# PCB0M3_12B.net
KiCad netlist of a schematic drawn in EAGLE
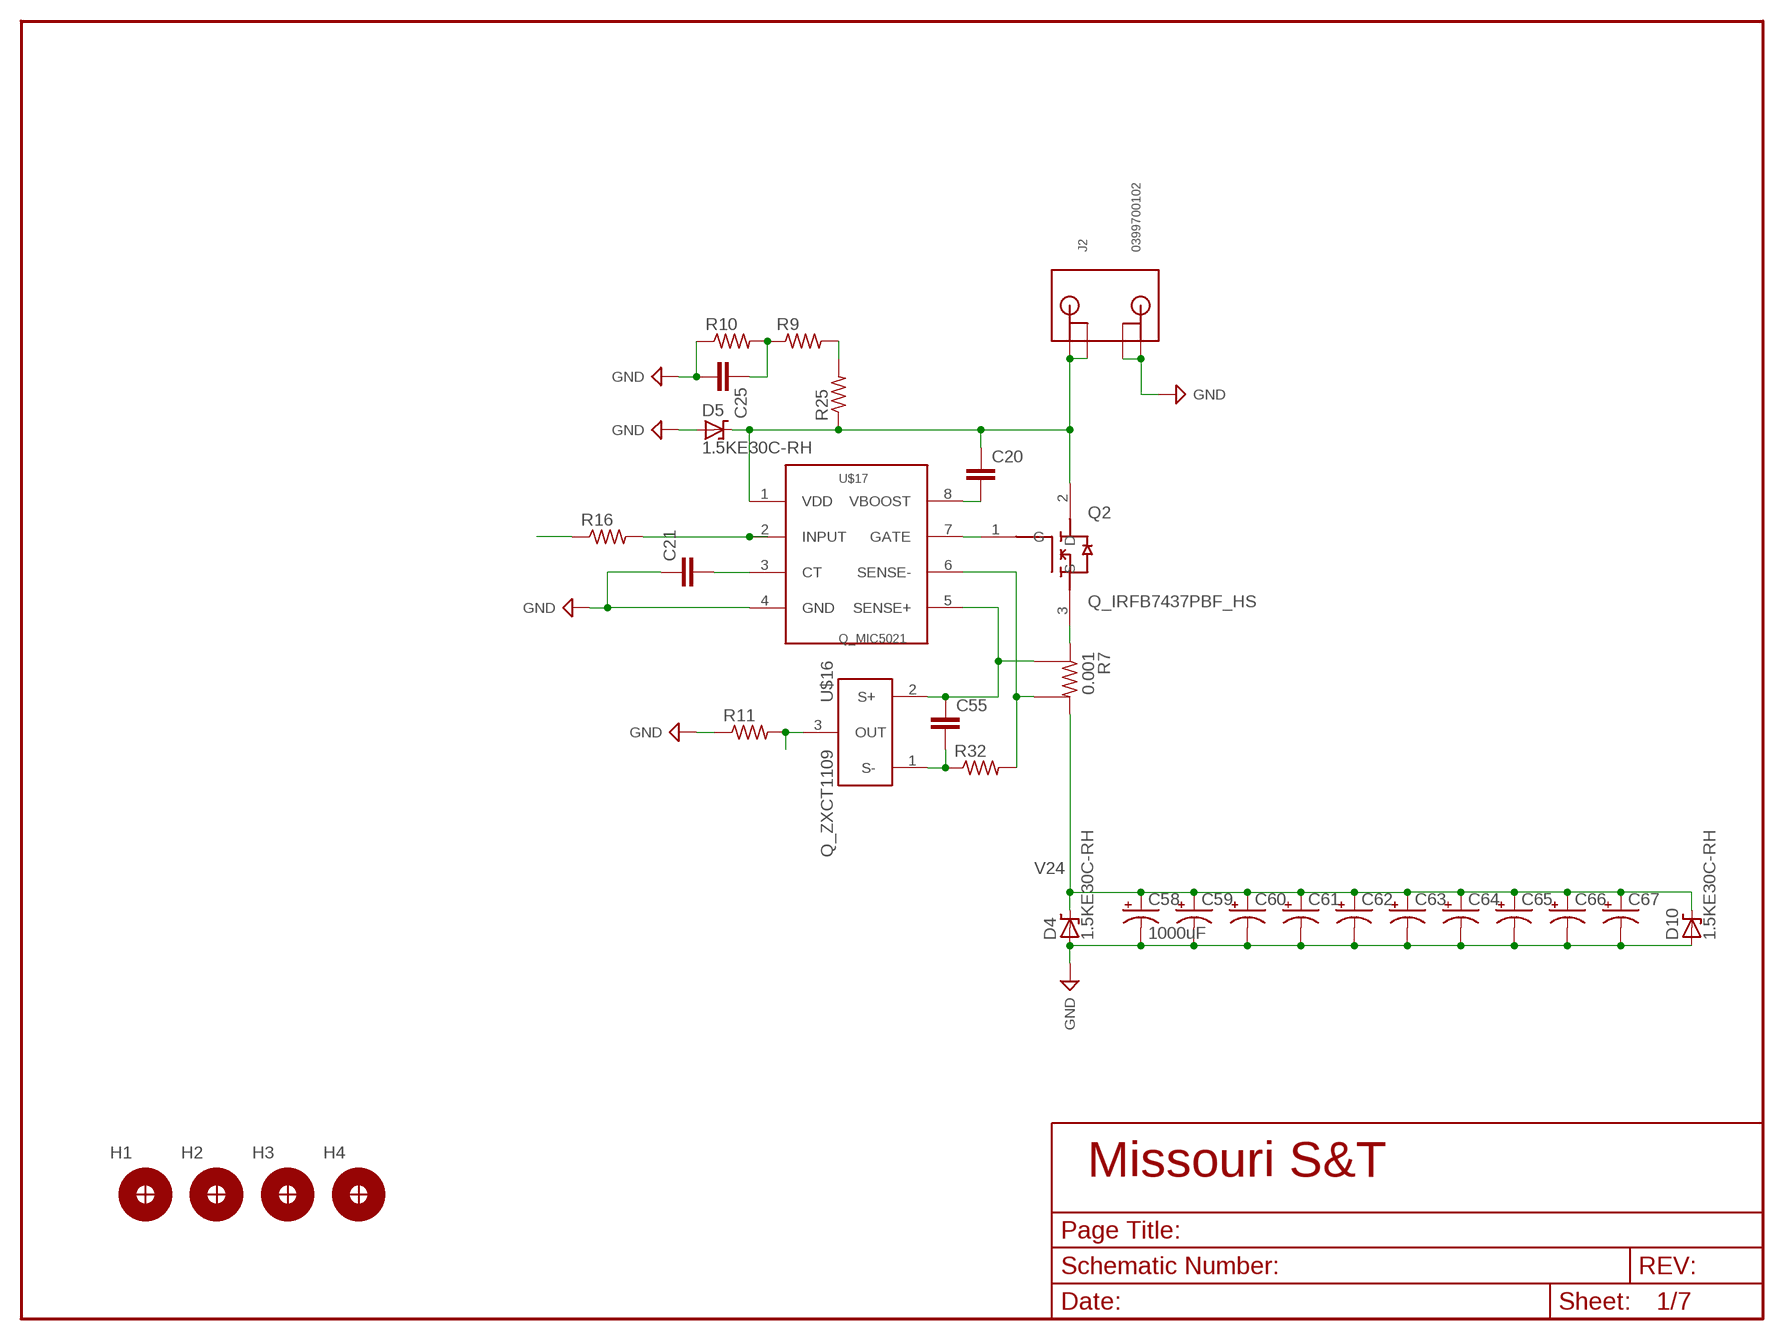
[diagram p0: schematic, sheet 1]
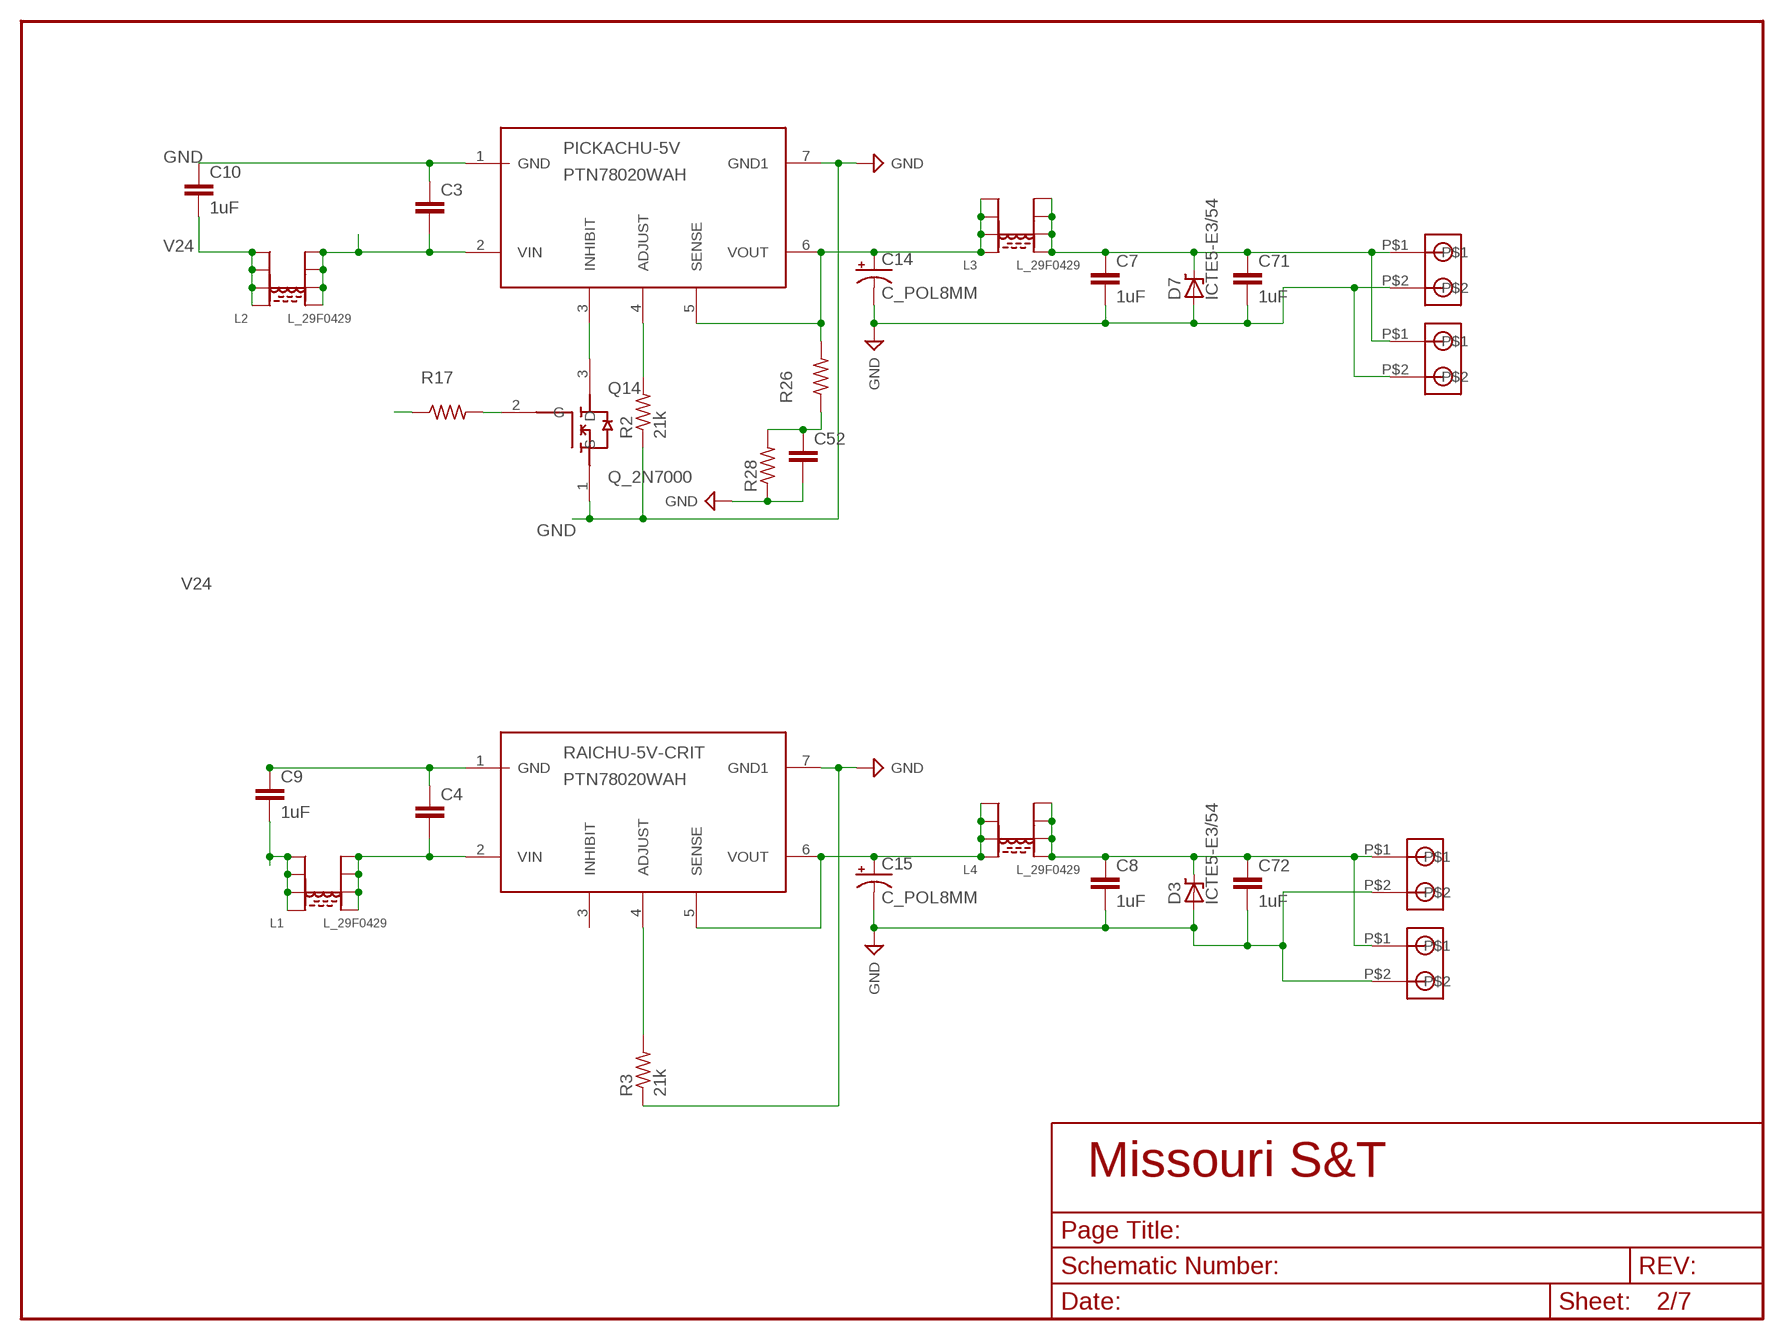
[diagram p1: schematic, sheet 2]
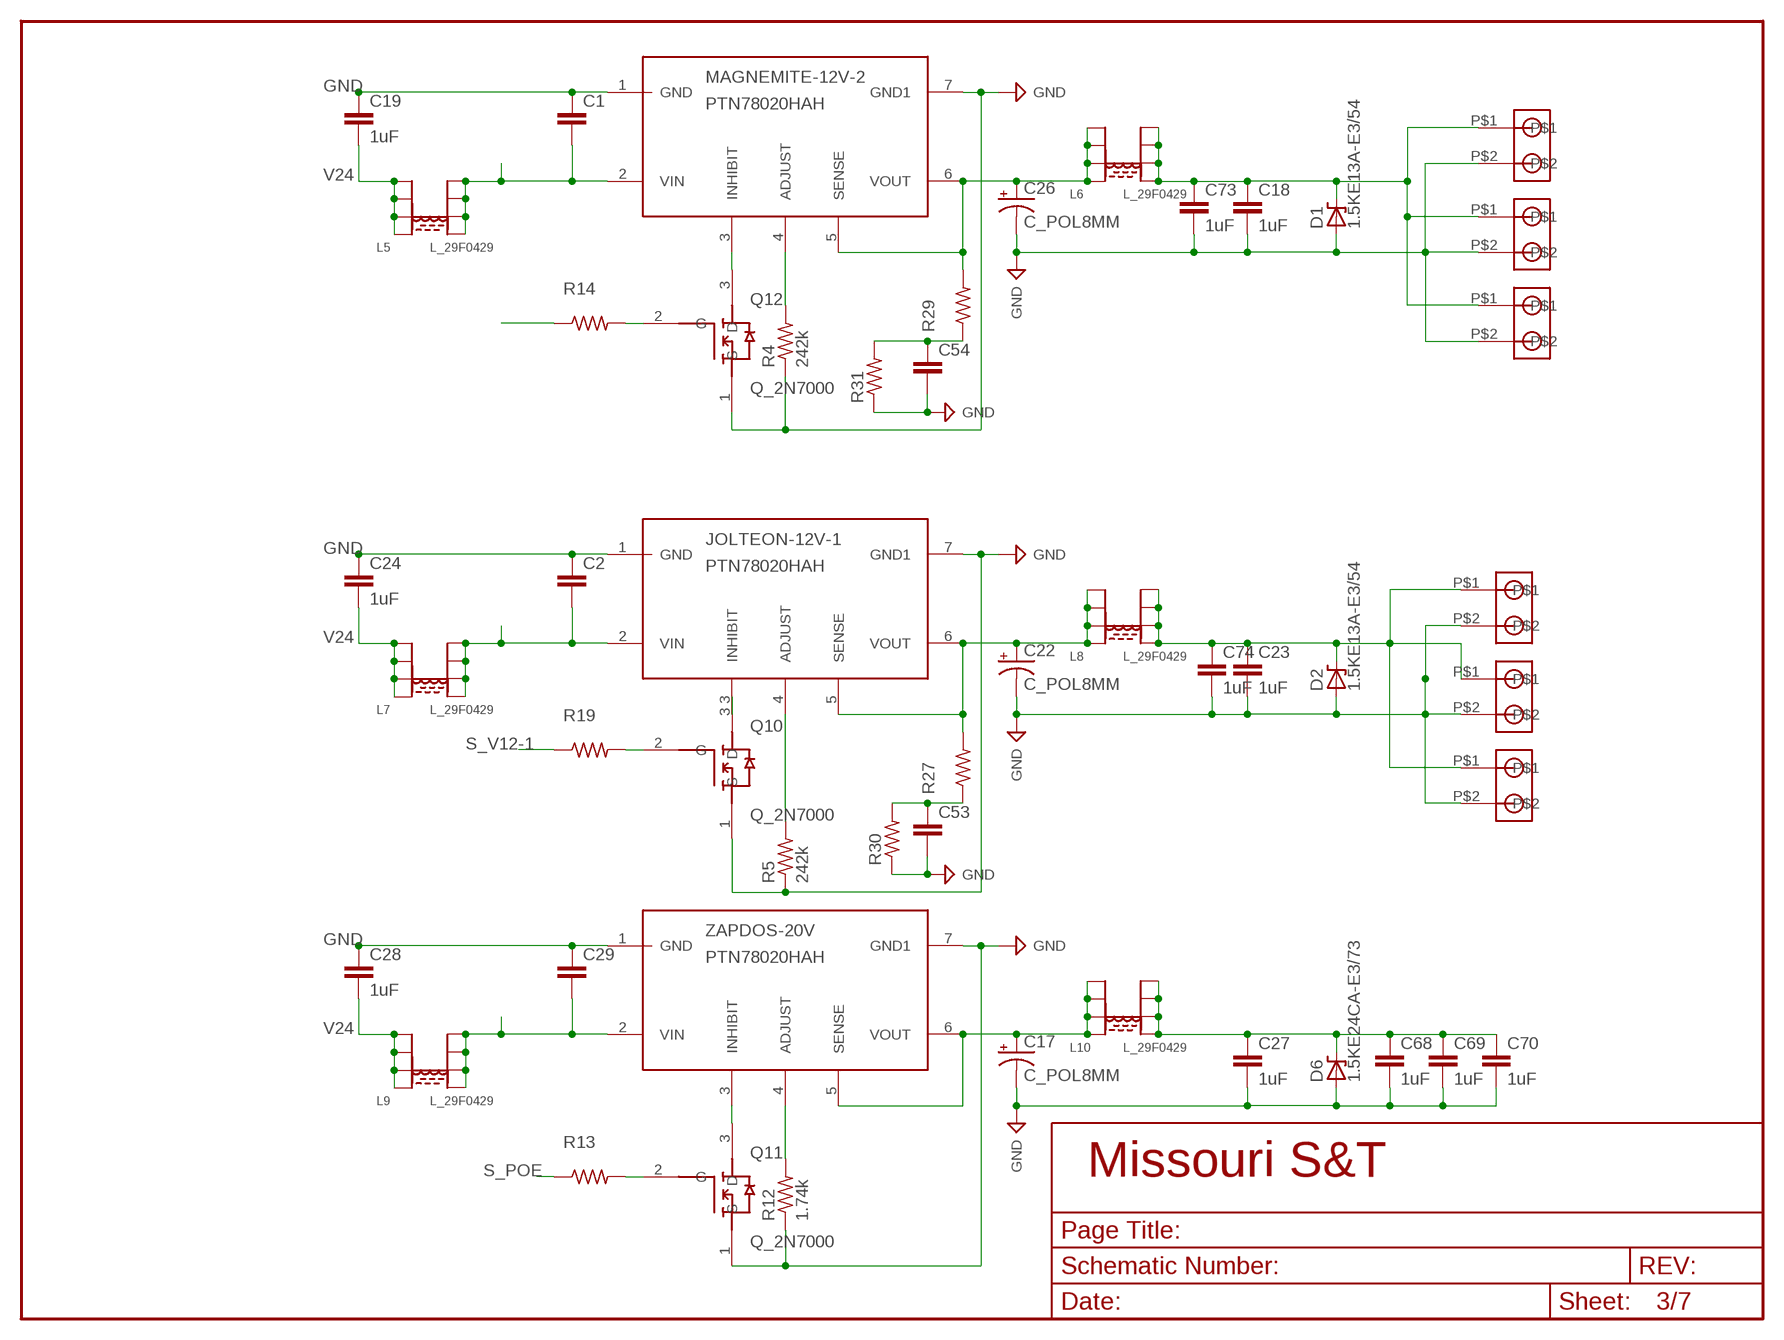
[diagram p2: schematic, sheet 3]
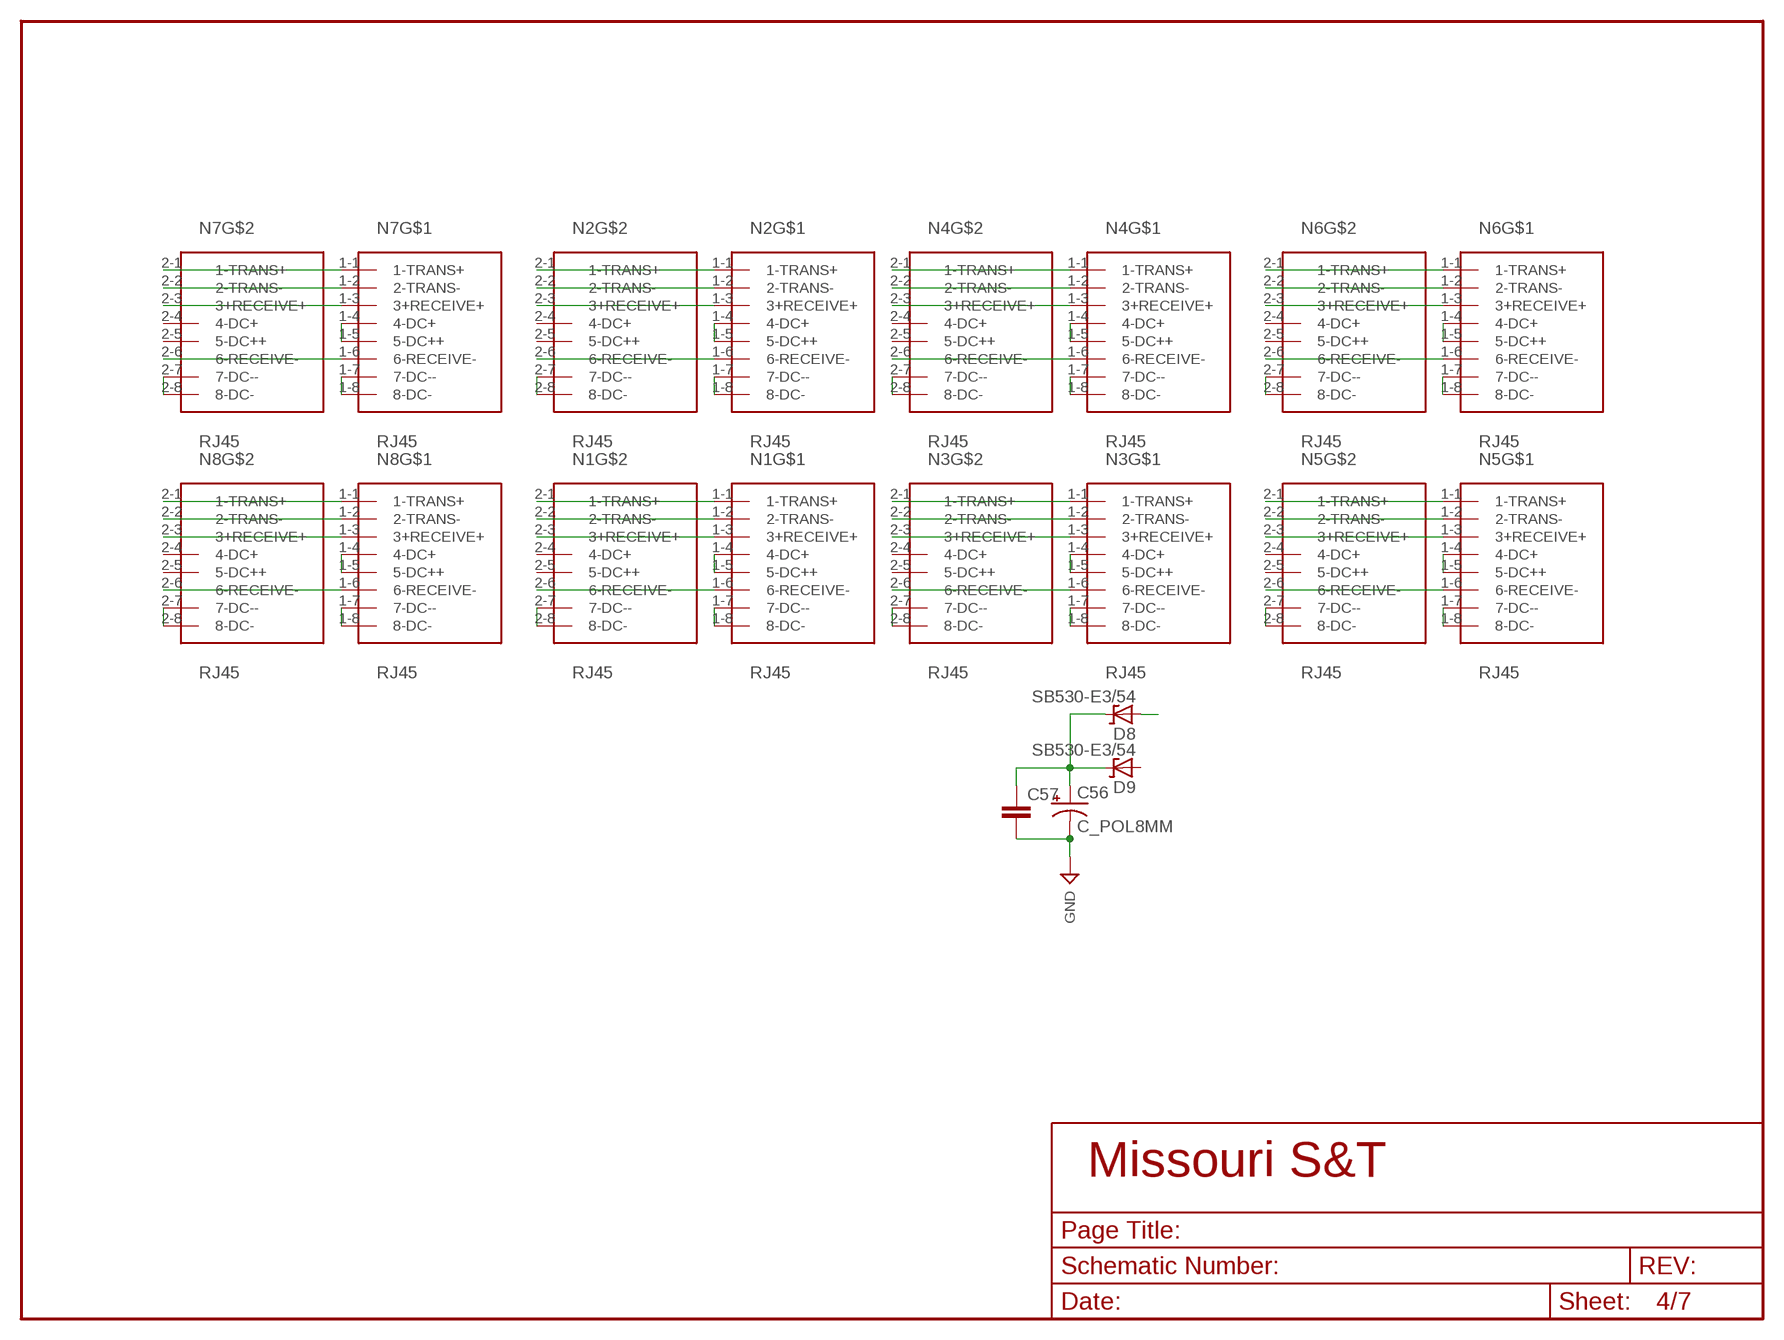
[diagram p3: schematic, sheet 4]
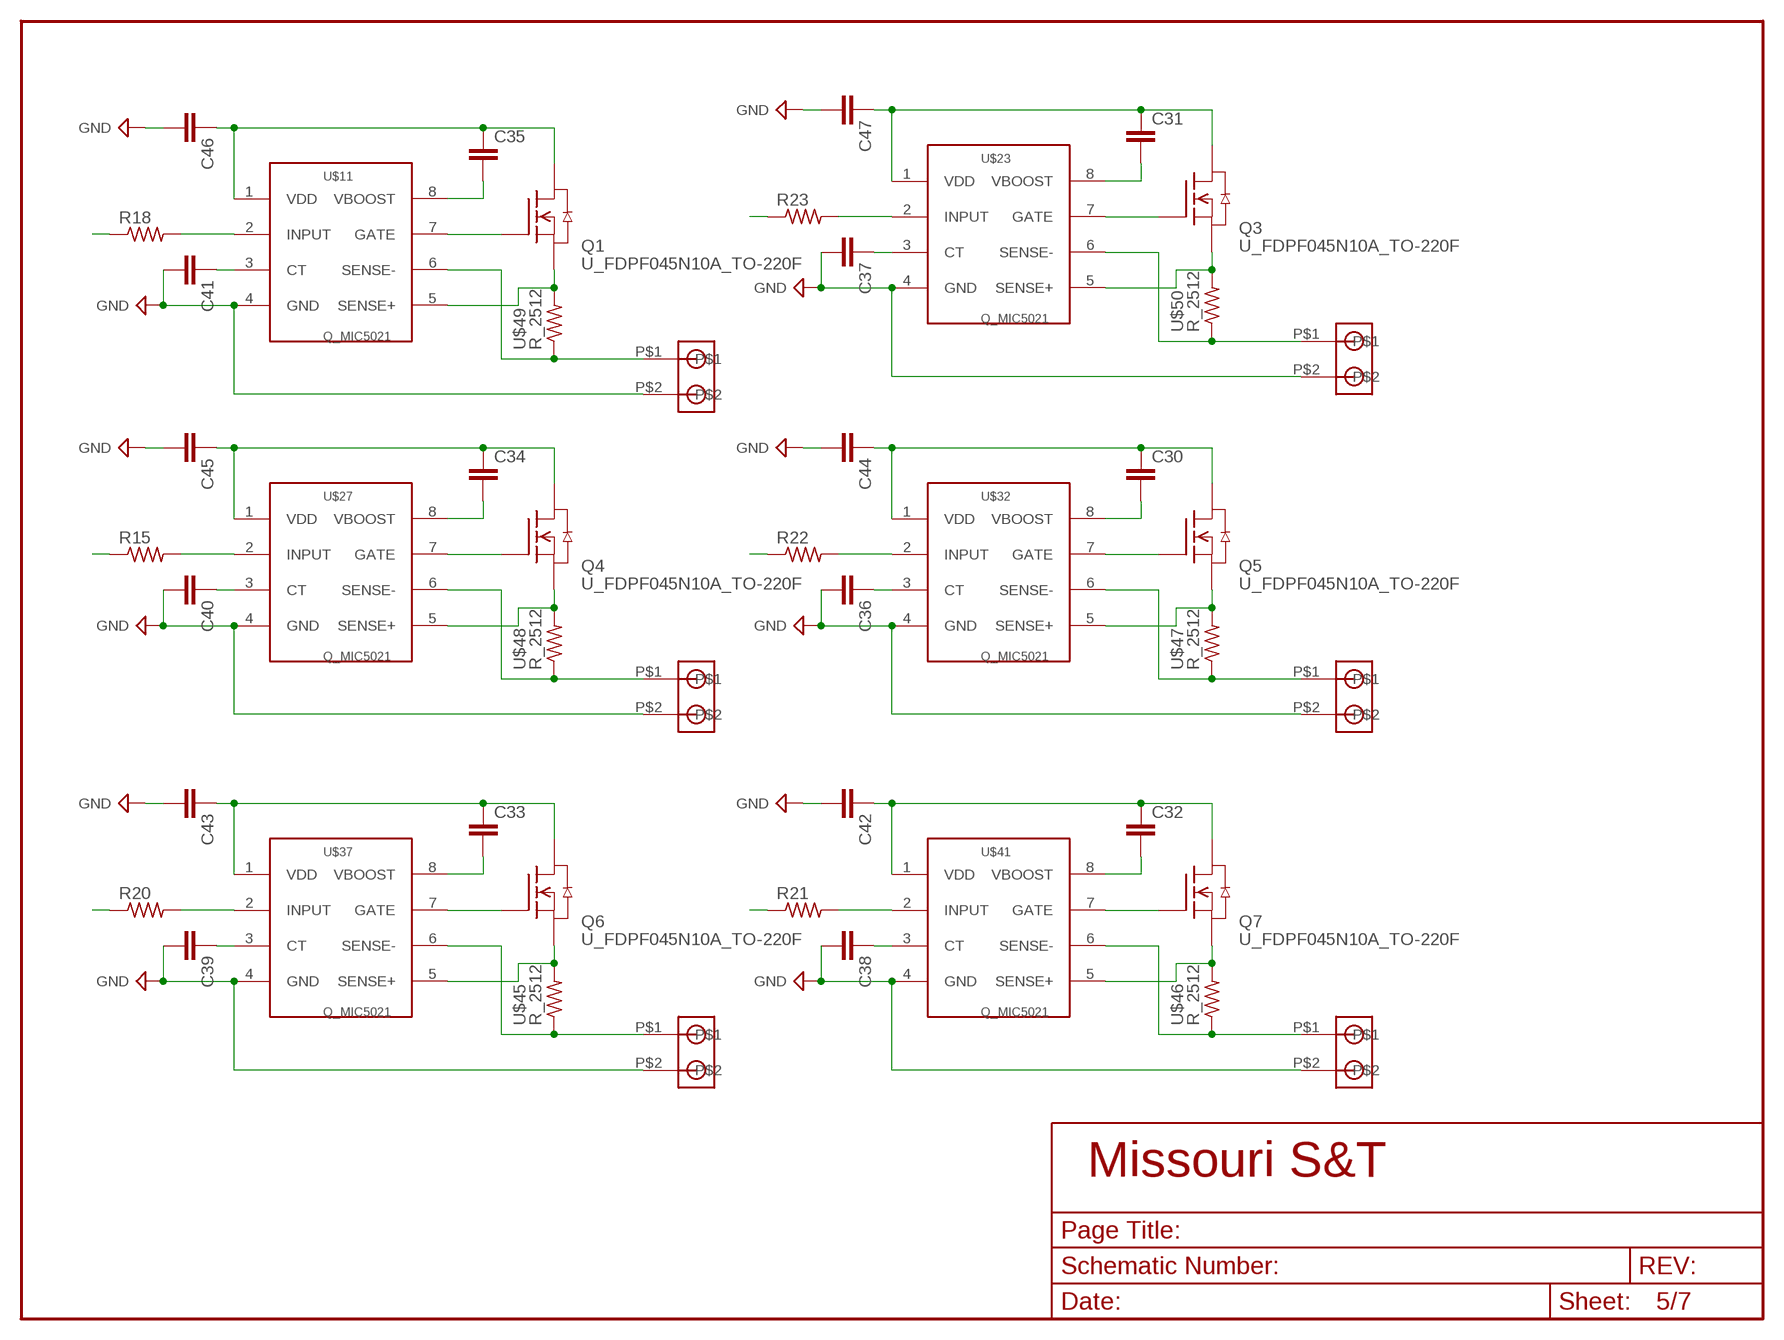
[diagram p4: schematic, sheet 5]
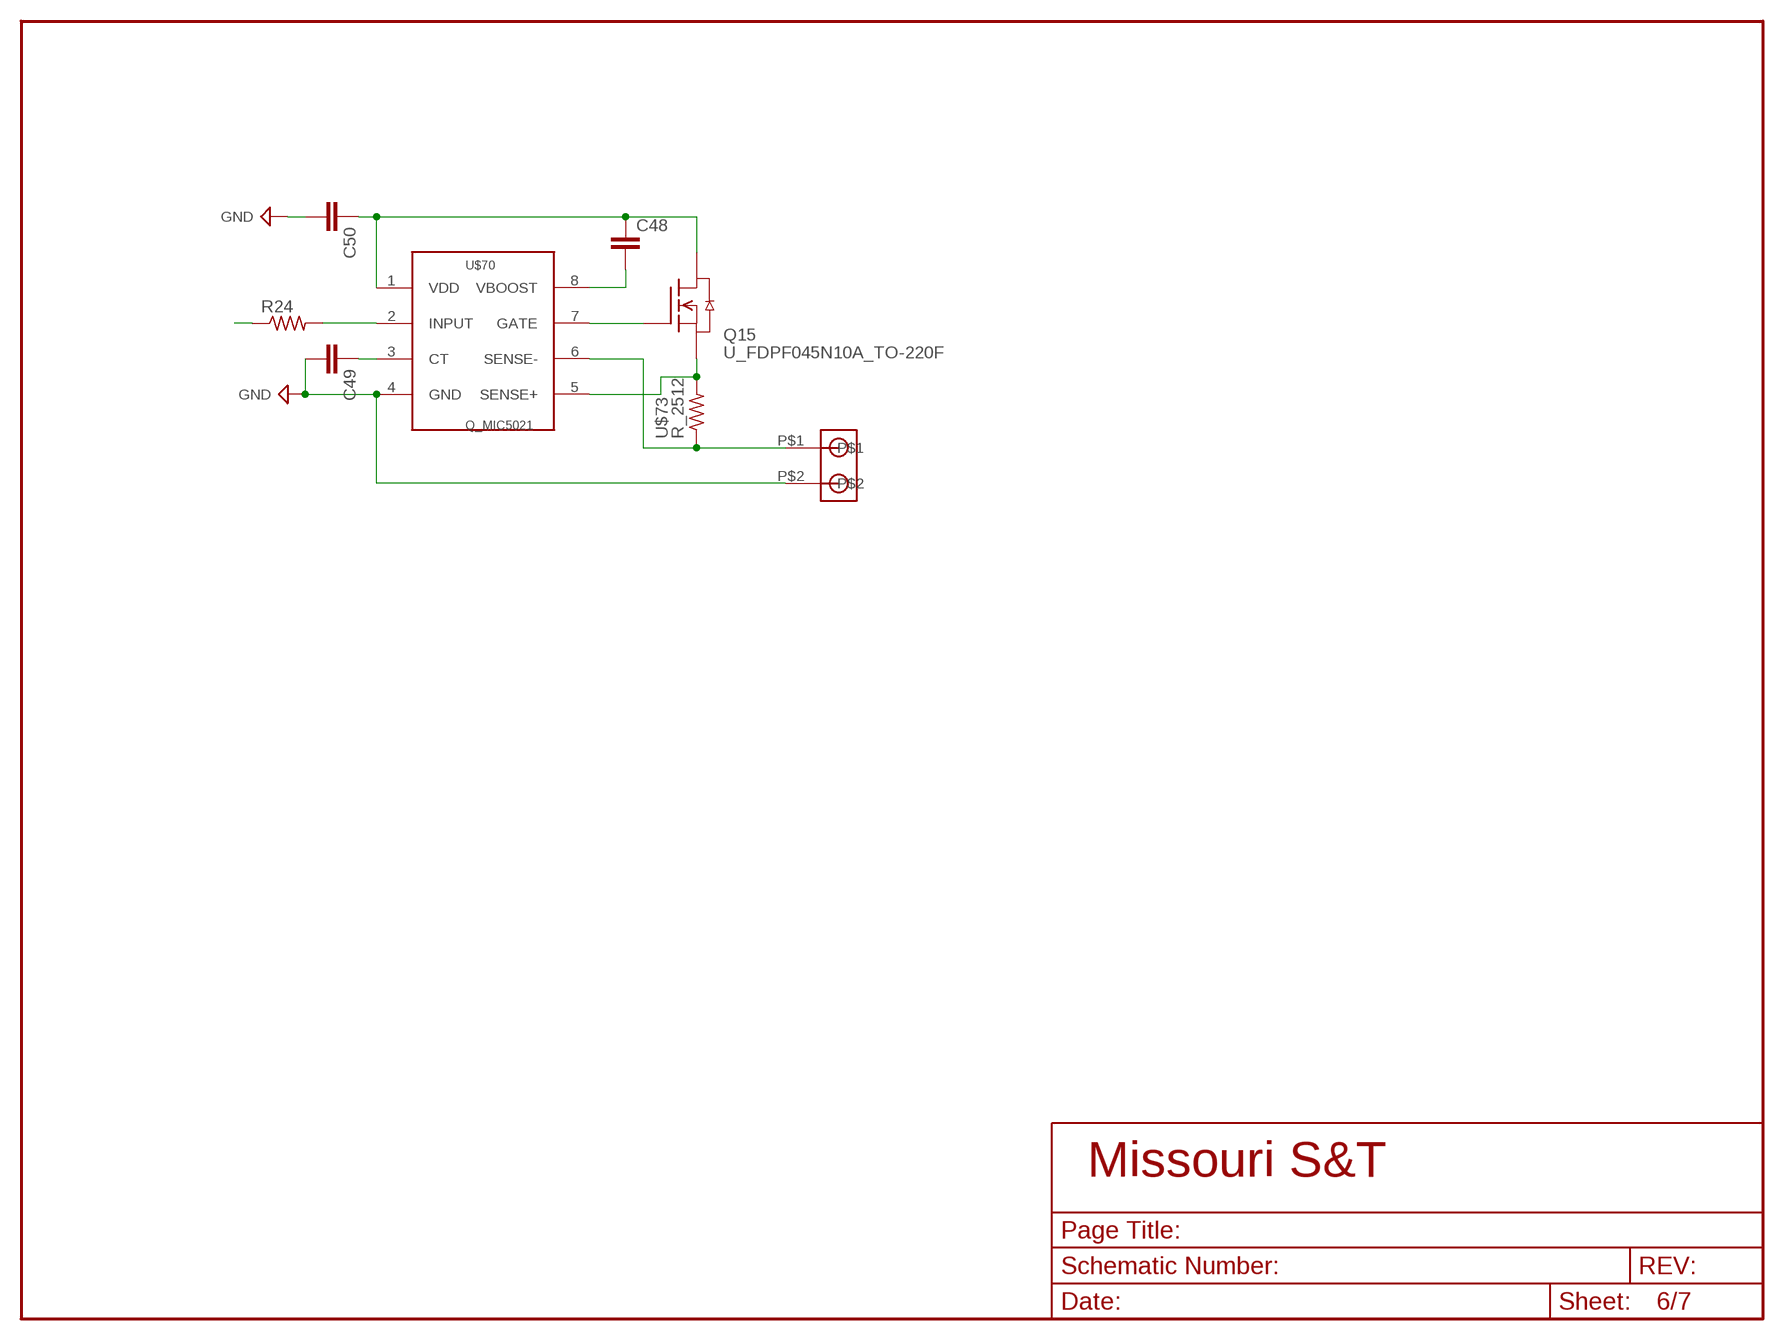
[diagram p5: schematic, sheet 6]
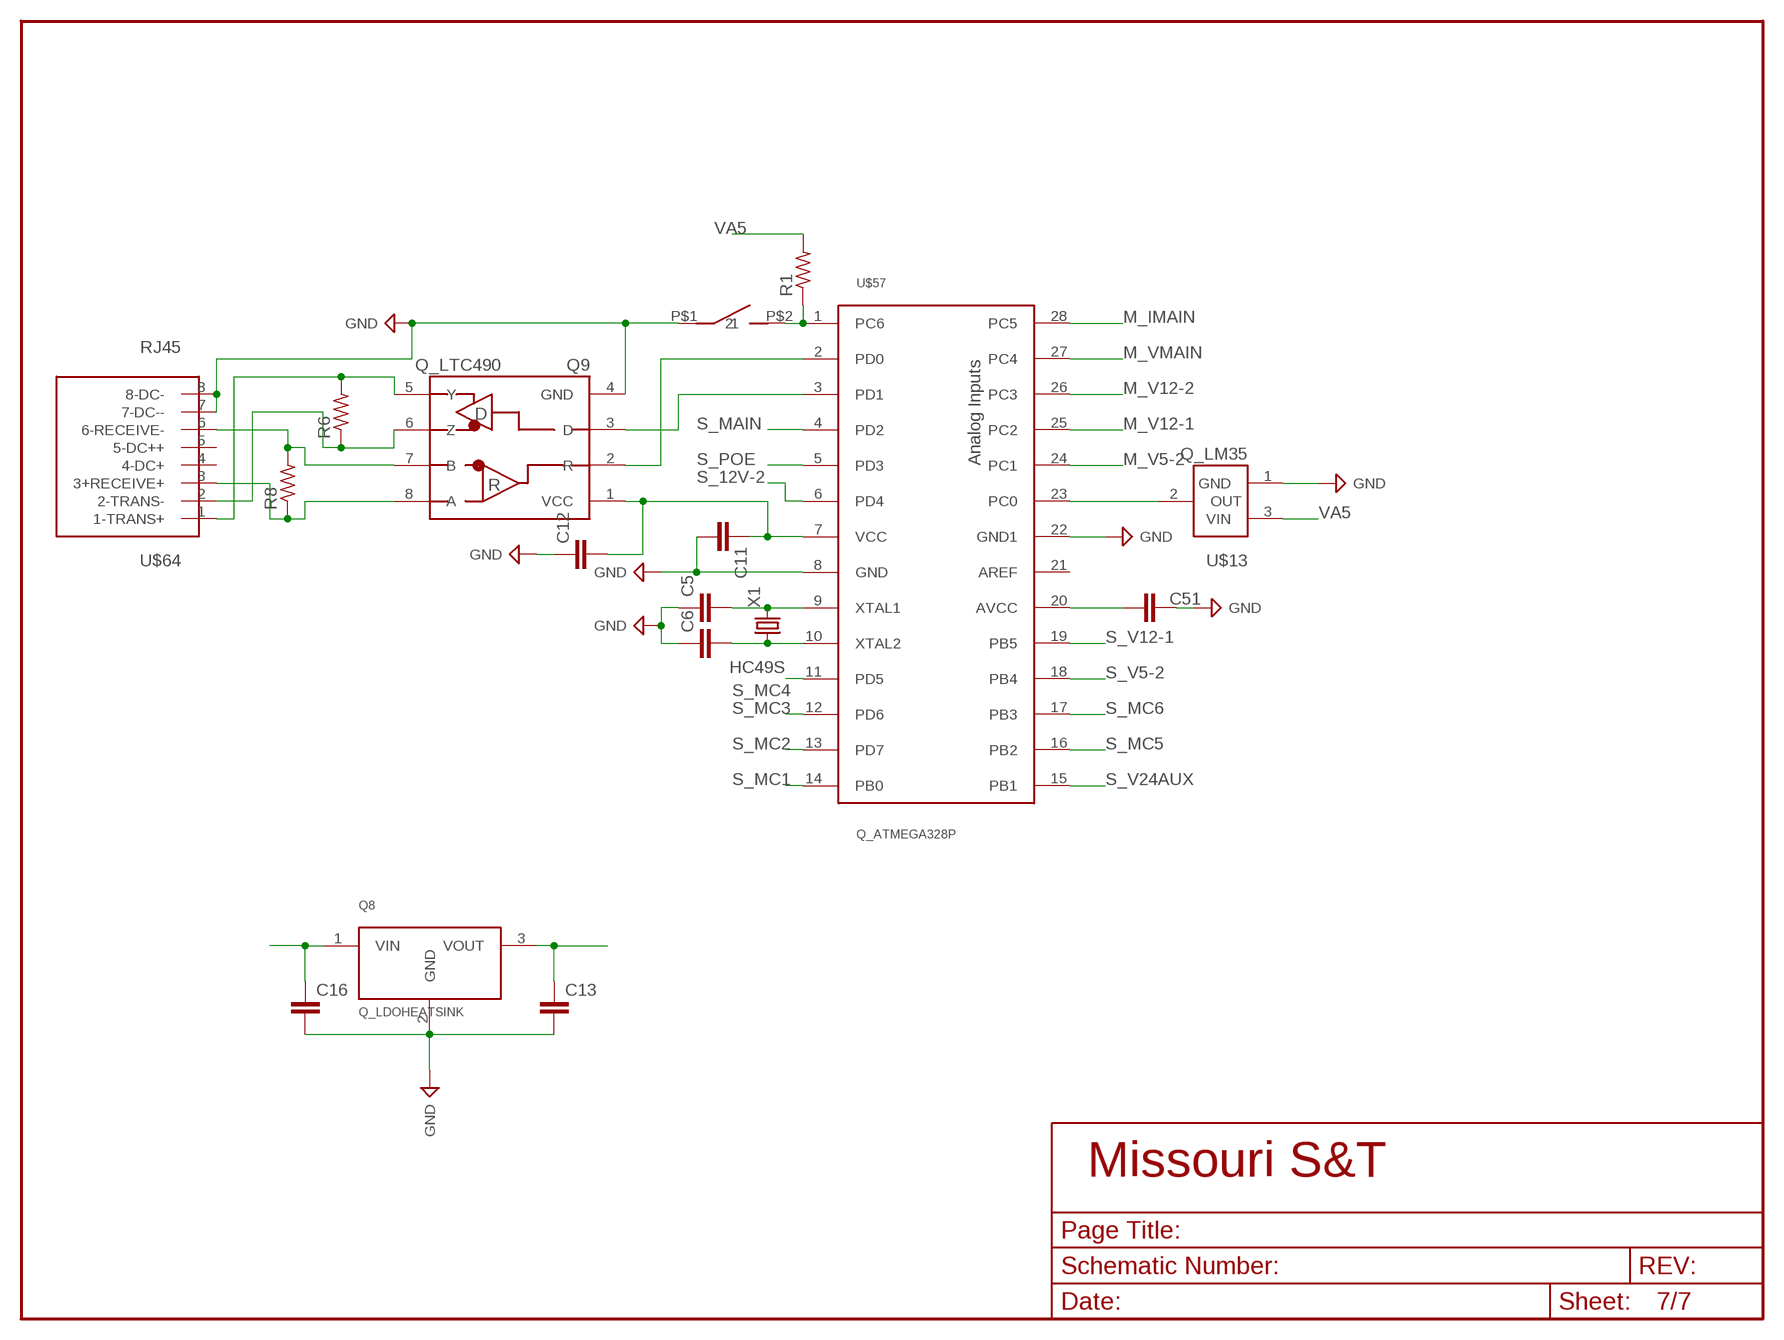
[diagram p6: schematic, sheet 7]

(export (version "E")
  (design (tool "Eeschema 10.0.6"))
  (components
    (comp (ref "C1")
      (value "C_CAP_1206")
      (footprint "eagle-import:C_1206")
      (libsource (lib "eagle-import") (part "C_CAP_1206"))
    )
    (comp (ref "C2")
      (value "C_CAP_1206")
      (footprint "eagle-import:C_1206")
      (libsource (lib "eagle-import") (part "C_CAP_1206"))
    )
    (comp (ref "C17")
      (value "C_POL8MM")
      (footprint "eagle-import:C_8MM")
      (libsource (lib "eagle-import") (part "C_POL8MM"))
    )
    (comp (ref "C18")
      (value "1uF")
      (footprint "eagle-import:C_1206")
      (libsource (lib "eagle-import") (part "C_CAP_1206"))
    )
    (comp (ref "C19")
      (value "1uF")
      (footprint "eagle-import:C_1206")
      (libsource (lib "eagle-import") (part "C_CAP_1206"))
    )
    (comp (ref "C22")
      (value "C_POL8MM")
      (footprint "eagle-import:C_8MM")
      (libsource (lib "eagle-import") (part "C_POL8MM"))
    )
    (comp (ref "C23")
      (value "1uF")
      (footprint "eagle-import:C_1206")
      (libsource (lib "eagle-import") (part "C_CAP_1206"))
    )
    (comp (ref "C24")
      (value "1uF")
      (footprint "eagle-import:C_1206")
      (libsource (lib "eagle-import") (part "C_CAP_1206"))
    )
    (comp (ref "C26")
      (value "C_POL8MM")
      (footprint "eagle-import:C_8MM")
      (libsource (lib "eagle-import") (part "C_POL8MM"))
    )
    (comp (ref "C27")
      (value "1uF")
      (footprint "eagle-import:C_1206")
      (libsource (lib "eagle-import") (part "C_CAP_1206"))
    )
    (comp (ref "C28")
      (value "1uF")
      (footprint "eagle-import:C_1206")
      (libsource (lib "eagle-import") (part "C_CAP_1206"))
    )
    (comp (ref "C29")
      (value "C_CAP_1206")
      (footprint "eagle-import:C_1206")
      (libsource (lib "eagle-import") (part "C_CAP_1206"))
    )
    (comp (ref "C53")
      (value "C_CAP_1206")
      (footprint "eagle-import:C_1206")
      (libsource (lib "eagle-import") (part "C_CAP_1206"))
    )
    (comp (ref "C54")
      (value "C_CAP_1206")
      (footprint "eagle-import:C_1206")
      (libsource (lib "eagle-import") (part "C_CAP_1206"))
    )
    (comp (ref "C68")
      (value "1uF")
      (footprint "eagle-import:C_1206")
      (libsource (lib "eagle-import") (part "C_CAP_1206"))
    )
    (comp (ref "C69")
      (value "1uF")
      (footprint "eagle-import:C_1206")
      (libsource (lib "eagle-import") (part "C_CAP_1206"))
    )
    (comp (ref "C70")
      (value "1uF")
      (footprint "eagle-import:C_1206")
      (libsource (lib "eagle-import") (part "C_CAP_1206"))
    )
    (comp (ref "C73")
      (value "1uF")
      (footprint "eagle-import:C_1206")
      (libsource (lib "eagle-import") (part "C_CAP_1206"))
    )
    (comp (ref "C74")
      (value "1uF")
      (footprint "eagle-import:C_1206")
      (libsource (lib "eagle-import") (part "C_CAP_1206"))
    )
    (comp (ref "D1")
      (value "1.5KE13A-E3/54")
      (footprint "eagle-import:DIODE_D3.5MM_LS15.24MM")
      (libsource (lib "eagle-import") (part "D_1.5KE480A_D3.5MM_LS15.24MM"))
    )
    (comp (ref "D2")
      (value "1.5KE13A-E3/54")
      (footprint "eagle-import:DIODE_D3.5MM_LS15.24MM")
      (libsource (lib "eagle-import") (part "D_1.5KE480A_D3.5MM_LS15.24MM"))
    )
    (comp (ref "D6")
      (value "1.5KE24CA-E3/73")
      (footprint "eagle-import:DIODE_D3.5MM_LS15.24MM")
      (libsource (lib "eagle-import") (part "D_1.5KE480A_D3.5MM_LS15.24MM"))
    )
    (comp (ref "J3")
      (value "J_1546074-2282834-2")
      (footprint "eagle-import:J_2.54MM")
      (libsource (lib "eagle-import") (part "J_1546074-2282834-2"))
    )
    (comp (ref "J4")
      (value "J_1546074-2282834-2")
      (footprint "eagle-import:J_2.54MM")
      (libsource (lib "eagle-import") (part "J_1546074-2282834-2"))
    )
    (comp (ref "J5")
      (value "J_1546074-2282834-2")
      (footprint "eagle-import:J_2.54MM")
      (libsource (lib "eagle-import") (part "J_1546074-2282834-2"))
    )
    (comp (ref "J6")
      (value "J_1546074-2282834-2")
      (footprint "eagle-import:J_2.54MM")
      (libsource (lib "eagle-import") (part "J_1546074-2282834-2"))
    )
    (comp (ref "J7")
      (value "J_1546074-2282834-2")
      (footprint "eagle-import:J_2.54MM")
      (libsource (lib "eagle-import") (part "J_1546074-2282834-2"))
    )
    (comp (ref "J8")
      (value "J_1546074-2282834-2")
      (footprint "eagle-import:J_2.54MM")
      (libsource (lib "eagle-import") (part "J_1546074-2282834-2"))
    )
    (comp (ref "JOLTEON-12V-1")
      (value "PTN78020HAH")
      (footprint "eagle-import:R_PDSS-T7")
      (libsource (lib "eagle-import") (part "Q_PTN78020"))
    )
    (comp (ref "L5")
      (value "L_29F0429")
      (footprint "eagle-import:L_29F0429")
      (libsource (lib "eagle-import") (part "L_29F0429"))
    )
    (comp (ref "L6")
      (value "L_29F0429")
      (footprint "eagle-import:L_29F0429")
      (libsource (lib "eagle-import") (part "L_29F0429"))
    )
    (comp (ref "L7")
      (value "L_29F0429")
      (footprint "eagle-import:L_29F0429")
      (libsource (lib "eagle-import") (part "L_29F0429"))
    )
    (comp (ref "L8")
      (value "L_29F0429")
      (footprint "eagle-import:L_29F0429")
      (libsource (lib "eagle-import") (part "L_29F0429"))
    )
    (comp (ref "L9")
      (value "L_29F0429")
      (footprint "eagle-import:L_29F0429")
      (libsource (lib "eagle-import") (part "L_29F0429"))
    )
    (comp (ref "L10")
      (value "L_29F0429")
      (footprint "eagle-import:L_29F0429")
      (libsource (lib "eagle-import") (part "L_29F0429"))
    )
    (comp (ref "MAGNEMITE-12V-2")
      (value "PTN78020HAH")
      (footprint "eagle-import:R_PDSS-T7")
      (libsource (lib "eagle-import") (part "Q_PTN78020"))
    )
    (comp (ref "Q10")
      (value "Q_2N7000")
      (footprint "eagle-import:TO-92-3")
      (libsource (lib "eagle-import") (part "Q_2N7000"))
    )
    (comp (ref "Q11")
      (value "Q_2N7000")
      (footprint "eagle-import:TO-92-3")
      (libsource (lib "eagle-import") (part "Q_2N7000"))
    )
    (comp (ref "Q12")
      (value "Q_2N7000")
      (footprint "eagle-import:TO-92-3")
      (libsource (lib "eagle-import") (part "Q_2N7000"))
    )
    (comp (ref "R4")
      (value "242k")
      (footprint "eagle-import:R_1_4W")
      (libsource (lib "eagle-import") (part "R_1/4W"))
    )
    (comp (ref "R5")
      (value "242k")
      (footprint "eagle-import:R_1_4W")
      (libsource (lib "eagle-import") (part "R_1/4W"))
    )
    (comp (ref "R12")
      (value "1.74k")
      (footprint "eagle-import:R_1_4W")
      (libsource (lib "eagle-import") (part "R_1/4W"))
    )
    (comp (ref "R13")
      (value "R_1/4WL")
      (footprint "eagle-import:R_1_4WL")
      (libsource (lib "eagle-import") (part "R_1/4WL"))
    )
    (comp (ref "R14")
      (value "R_1/4WL")
      (footprint "eagle-import:R_1_4WL")
      (libsource (lib "eagle-import") (part "R_1/4WL"))
    )
    (comp (ref "R19")
      (value "R_1/4WL")
      (footprint "eagle-import:R_1_4WL")
      (libsource (lib "eagle-import") (part "R_1/4WL"))
    )
    (comp (ref "R27")
      (value "R_1/4WL")
      (footprint "eagle-import:R_1_4WL")
      (libsource (lib "eagle-import") (part "R_1/4WL"))
    )
    (comp (ref "R29")
      (value "R_1/4WL")
      (footprint "eagle-import:R_1_4WL")
      (libsource (lib "eagle-import") (part "R_1/4WL"))
    )
    (comp (ref "R30")
      (value "R_RES_1206")
      (footprint "eagle-import:R_1206")
      (libsource (lib "eagle-import") (part "R_RES_1206"))
    )
    (comp (ref "R31")
      (value "R_RES_1206")
      (footprint "eagle-import:R_1206")
      (libsource (lib "eagle-import") (part "R_RES_1206"))
    )
    (comp (ref "ZAPDOS-20V")
      (value "PTN78020HAH")
      (footprint "eagle-import:R_PDSS-T7")
      (libsource (lib "eagle-import") (part "Q_PTN78020"))
    )
    (comp (ref "C56")
      (value "C_POL8MM")
      (footprint "eagle-import:C_8MM")
      (libsource (lib "eagle-import") (part "C_POL8MM"))
    )
    (comp (ref "C57")
      (value "C_CAP_1206")
      (footprint "eagle-import:C_1206")
      (libsource (lib "eagle-import") (part "C_CAP_1206"))
    )
    (comp (ref "D8")
      (value "SB530-E3/54")
      (footprint "eagle-import:DIODE_D3.5MM_LS15.24MM")
      (libsource (lib "eagle-import") (part "D_1.5KE480A_D3.5MM_LS15.24MM"))
    )
    (comp (ref "D9")
      (value "SB530-E3/54")
      (footprint "eagle-import:DIODE_D3.5MM_LS15.24MM")
      (libsource (lib "eagle-import") (part "D_1.5KE480A_D3.5MM_LS15.24MM"))
    )
    (comp (ref "N1")
      (value "RJ45")
      (footprint "eagle-import:RJ45-CAT5E-2PACK")
      (libsource (lib "eagle-import") (part "RJ45-2PORT"))
    )
    (comp (ref "N2")
      (value "RJ45")
      (footprint "eagle-import:RJ45-CAT5E-2PACK")
      (libsource (lib "eagle-import") (part "RJ45-2PORT"))
    )
    (comp (ref "N3")
      (value "RJ45")
      (footprint "eagle-import:RJ45-CAT5E-2PACK")
      (libsource (lib "eagle-import") (part "RJ45-2PORT"))
    )
    (comp (ref "N4")
      (value "RJ45")
      (footprint "eagle-import:RJ45-CAT5E-2PACK")
      (libsource (lib "eagle-import") (part "RJ45-2PORT"))
    )
    (comp (ref "N5")
      (value "RJ45")
      (footprint "eagle-import:RJ45-CAT5E-2PACK")
      (libsource (lib "eagle-import") (part "RJ45-2PORT"))
    )
    (comp (ref "N6")
      (value "RJ45")
      (footprint "eagle-import:RJ45-CAT5E-2PACK")
      (libsource (lib "eagle-import") (part "RJ45-2PORT"))
    )
    (comp (ref "N7")
      (value "RJ45")
      (footprint "eagle-import:RJ45-CAT5E-2PACK")
      (libsource (lib "eagle-import") (part "RJ45-2PORT"))
    )
    (comp (ref "N8")
      (value "RJ45")
      (footprint "eagle-import:RJ45-CAT5E-2PACK")
      (libsource (lib "eagle-import") (part "RJ45-2PORT"))
    )
    (comp (ref "C3")
      (value "C_CAP_1206")
      (footprint "eagle-import:C_1206")
      (libsource (lib "eagle-import") (part "C_CAP_1206"))
    )
    (comp (ref "C4")
      (value "C_CAP_1206")
      (footprint "eagle-import:C_1206")
      (libsource (lib "eagle-import") (part "C_CAP_1206"))
    )
    (comp (ref "C7")
      (value "1uF")
      (footprint "eagle-import:C_1206")
      (libsource (lib "eagle-import") (part "C_CAP_1206"))
    )
    (comp (ref "C8")
      (value "1uF")
      (footprint "eagle-import:C_1206")
      (libsource (lib "eagle-import") (part "C_CAP_1206"))
    )
    (comp (ref "C9")
      (value "1uF")
      (footprint "eagle-import:C_1206")
      (libsource (lib "eagle-import") (part "C_CAP_1206"))
    )
    (comp (ref "C10")
      (value "1uF")
      (footprint "eagle-import:C_1206")
      (libsource (lib "eagle-import") (part "C_CAP_1206"))
    )
    (comp (ref "C14")
      (value "C_POL8MM")
      (footprint "eagle-import:C_8MM")
      (libsource (lib "eagle-import") (part "C_POL8MM"))
    )
    (comp (ref "C15")
      (value "C_POL8MM")
      (footprint "eagle-import:C_8MM")
      (libsource (lib "eagle-import") (part "C_POL8MM"))
    )
    (comp (ref "C52")
      (value "C_CAP_1206")
      (footprint "eagle-import:C_1206")
      (libsource (lib "eagle-import") (part "C_CAP_1206"))
    )
    (comp (ref "C71")
      (value "1uF")
      (footprint "eagle-import:C_1206")
      (libsource (lib "eagle-import") (part "C_CAP_1206"))
    )
    (comp (ref "C72")
      (value "1uF")
      (footprint "eagle-import:C_1206")
      (libsource (lib "eagle-import") (part "C_CAP_1206"))
    )
    (comp (ref "D3")
      (value "ICTE5-E3/54")
      (footprint "eagle-import:DIODE_D3.5MM_LS15.24MM")
      (libsource (lib "eagle-import") (part "D_1.5KE480A_D3.5MM_LS15.24MM"))
    )
    (comp (ref "D7")
      (value "ICTE5-E3/54")
      (footprint "eagle-import:DIODE_D3.5MM_LS15.24MM")
      (libsource (lib "eagle-import") (part "D_1.5KE480A_D3.5MM_LS15.24MM"))
    )
    (comp (ref "L1")
      (value "L_29F0429")
      (footprint "eagle-import:L_29F0429")
      (libsource (lib "eagle-import") (part "L_29F0429"))
    )
    (comp (ref "L2")
      (value "L_29F0429")
      (footprint "eagle-import:L_29F0429")
      (libsource (lib "eagle-import") (part "L_29F0429"))
    )
    (comp (ref "L3")
      (value "L_29F0429")
      (footprint "eagle-import:L_29F0429")
      (libsource (lib "eagle-import") (part "L_29F0429"))
    )
    (comp (ref "L4")
      (value "L_29F0429")
      (footprint "eagle-import:L_29F0429")
      (libsource (lib "eagle-import") (part "L_29F0429"))
    )
    (comp (ref "PICKACHU-5V")
      (value "PTN78020WAH")
      (footprint "eagle-import:R_PDSS-T7")
      (libsource (lib "eagle-import") (part "Q_PTN78020"))
    )
    (comp (ref "Q14")
      (value "Q_2N7000")
      (footprint "eagle-import:TO-92-3")
      (libsource (lib "eagle-import") (part "Q_2N7000"))
    )
    (comp (ref "R2")
      (value "21k")
      (footprint "eagle-import:R_1_4W")
      (libsource (lib "eagle-import") (part "R_1/4W"))
    )
    (comp (ref "R3")
      (value "21k")
      (footprint "eagle-import:R_1_4W")
      (libsource (lib "eagle-import") (part "R_1/4W"))
    )
    (comp (ref "R17")
      (value "R_1/4WL")
      (footprint "eagle-import:R_1_4WL")
      (libsource (lib "eagle-import") (part "R_1/4WL"))
    )
    (comp (ref "R26")
      (value "R_1/4WL")
      (footprint "eagle-import:R_1_4WL")
      (libsource (lib "eagle-import") (part "R_1/4WL"))
    )
    (comp (ref "R28")
      (value "R_RES_1206")
      (footprint "eagle-import:R_1206")
      (libsource (lib "eagle-import") (part "R_RES_1206"))
    )
    (comp (ref "RAICHU-5V-CRIT")
      (value "PTN78020WAH")
      (footprint "eagle-import:R_PDSS-T7")
      (libsource (lib "eagle-import") (part "Q_PTN78020"))
    )
    (comp (ref "U$52")
      (value "J_1546074-2282834-2")
      (footprint "eagle-import:J_2.54MM")
      (libsource (lib "eagle-import") (part "J_1546074-2282834-2"))
    )
    (comp (ref "U$53")
      (value "J_1546074-2282834-2")
      (footprint "eagle-import:J_2.54MM")
      (libsource (lib "eagle-import") (part "J_1546074-2282834-2"))
    )
    (comp (ref "U$54")
      (value "J_1546074-2282834-2")
      (footprint "eagle-import:J_2.54MM")
      (libsource (lib "eagle-import") (part "J_1546074-2282834-2"))
    )
    (comp (ref "U$55")
      (value "J_1546074-2282834-2")
      (footprint "eagle-import:J_2.54MM")
      (libsource (lib "eagle-import") (part "J_1546074-2282834-2"))
    )
    (comp (ref "C20")
      (value "C_CAP_1206")
      (footprint "eagle-import:C_1206")
      (libsource (lib "eagle-import") (part "C_CAP_1206"))
    )
    (comp (ref "C21")
      (value "C_CAP_1206")
      (footprint "eagle-import:C_1206")
      (libsource (lib "eagle-import") (part "C_CAP_1206"))
    )
    (comp (ref "C25")
      (value "C_CAP_1206")
      (footprint "eagle-import:C_1206")
      (libsource (lib "eagle-import") (part "C_CAP_1206"))
    )
    (comp (ref "C55")
      (value "C_CAP_1206")
      (footprint "eagle-import:C_1206")
      (libsource (lib "eagle-import") (part "C_CAP_1206"))
    )
    (comp (ref "C58")
      (value "1000uF")
      (footprint "eagle-import:C_10MM")
      (libsource (lib "eagle-import") (part "C_POL10MM"))
    )
    (comp (ref "C59")
      (value "C_POL10MM")
      (footprint "eagle-import:C_10MM")
      (libsource (lib "eagle-import") (part "C_POL10MM"))
    )
    (comp (ref "C60")
      (value "C_POL10MM")
      (footprint "eagle-import:C_10MM")
      (libsource (lib "eagle-import") (part "C_POL10MM"))
    )
    (comp (ref "C61")
      (value "C_POL10MM")
      (footprint "eagle-import:C_10MM")
      (libsource (lib "eagle-import") (part "C_POL10MM"))
    )
    (comp (ref "C62")
      (value "C_POL10MM")
      (footprint "eagle-import:C_10MM")
      (libsource (lib "eagle-import") (part "C_POL10MM"))
    )
    (comp (ref "C63")
      (value "C_POL10MM")
      (footprint "eagle-import:C_10MM")
      (libsource (lib "eagle-import") (part "C_POL10MM"))
    )
    (comp (ref "C64")
      (value "C_POL10MM")
      (footprint "eagle-import:C_10MM")
      (libsource (lib "eagle-import") (part "C_POL10MM"))
    )
    (comp (ref "C65")
      (value "C_POL10MM")
      (footprint "eagle-import:C_10MM")
      (libsource (lib "eagle-import") (part "C_POL10MM"))
    )
    (comp (ref "C66")
      (value "C_POL10MM")
      (footprint "eagle-import:C_10MM")
      (libsource (lib "eagle-import") (part "C_POL10MM"))
    )
    (comp (ref "C67")
      (value "C_POL10MM")
      (footprint "eagle-import:C_10MM")
      (libsource (lib "eagle-import") (part "C_POL10MM"))
    )
    (comp (ref "D4")
      (value "1.5KE30C-RH")
      (footprint "eagle-import:DIODE_D3.5MM_LS15.24MM")
      (libsource (lib "eagle-import") (part "D_1.5KE480A_D3.5MM_LS15.24MM"))
    )
    (comp (ref "D5")
      (value "1.5KE30C-RH")
      (footprint "eagle-import:DIODE_D3.5MM_LS15.24MM")
      (libsource (lib "eagle-import") (part "D_1.5KE480A_D3.5MM_LS15.24MM"))
    )
    (comp (ref "D10")
      (value "1.5KE30C-RH")
      (footprint "eagle-import:DIODE_D3.5MM_LS15.24MM")
      (libsource (lib "eagle-import") (part "D_1.5KE480A_D3.5MM_LS15.24MM"))
    )
    (comp (ref "H1")
      (value "H_MNTHOLE_#8")
      (footprint "eagle-import:H_MNTHOLE_#8")
      (libsource (lib "eagle-import") (part "H_MNTHOLE_#8"))
    )
    (comp (ref "H2")
      (value "H_MNTHOLE_#8")
      (footprint "eagle-import:H_MNTHOLE_#8")
      (libsource (lib "eagle-import") (part "H_MNTHOLE_#8"))
    )
    (comp (ref "H3")
      (value "H_MNTHOLE_#8")
      (footprint "eagle-import:H_MNTHOLE_#8")
      (libsource (lib "eagle-import") (part "H_MNTHOLE_#8"))
    )
    (comp (ref "H4")
      (value "H_MNTHOLE_#8")
      (footprint "eagle-import:H_MNTHOLE_#8")
      (libsource (lib "eagle-import") (part "H_MNTHOLE_#8"))
    )
    (comp (ref "J2")
      (value "0399700102")
      (footprint "eagle-import:J_2CONHC")
      (libsource (lib "eagle-import") (part "J_0399700102"))
    )
    (comp (ref "Q2")
      (value "Q_IRFB7437PBF_HS")
      (footprint "eagle-import:TO-220-531102B02500G")
      (libsource (lib "eagle-import") (part "Q_IRFB7437PBF_HS"))
    )
    (comp (ref "R7")
      (value "0.001")
      (footprint "eagle-import:R_FC4L")
      (libsource (lib "eagle-import") (part "R_FC4L110R001JER"))
    )
    (comp (ref "R9")
      (value "R_RES_1206")
      (footprint "eagle-import:R_1206")
      (libsource (lib "eagle-import") (part "R_RES_1206"))
    )
    (comp (ref "R10")
      (value "R_RES_1206")
      (footprint "eagle-import:R_1206")
      (libsource (lib "eagle-import") (part "R_RES_1206"))
    )
    (comp (ref "R11")
      (value "R_RES_1206")
      (footprint "eagle-import:R_1206")
      (libsource (lib "eagle-import") (part "R_RES_1206"))
    )
    (comp (ref "R16")
      (value "R_RES_1206")
      (footprint "eagle-import:R_1206")
      (libsource (lib "eagle-import") (part "R_RES_1206"))
    )
    (comp (ref "R25")
      (value "R_1/4W")
      (footprint "eagle-import:R_1_4W")
      (libsource (lib "eagle-import") (part "R_1/4W"))
    )
    (comp (ref "R32")
      (value "R_RES_1206")
      (footprint "eagle-import:R_1206")
      (libsource (lib "eagle-import") (part "R_RES_1206"))
    )
    (comp (ref "U$16")
      (value "Q_ZXCT1109")
      (footprint "eagle-import:SOT23")
      (libsource (lib "eagle-import") (part "Q_ZXCT1109"))
    )
    (comp (ref "U$17")
      (value "Q_MIC5021")
      (footprint "eagle-import:DIP8")
      (libsource (lib "eagle-import") (part "Q_MIC5021"))
    )
    (comp (ref "C5")
      (value "C_CAP_1206")
      (footprint "eagle-import:C_1206")
      (libsource (lib "eagle-import") (part "C_CAP_1206"))
    )
    (comp (ref "C6")
      (value "C_CAP_1206")
      (footprint "eagle-import:C_1206")
      (libsource (lib "eagle-import") (part "C_CAP_1206"))
    )
    (comp (ref "C11")
      (value "C_CAP_1206")
      (footprint "eagle-import:C_1206")
      (libsource (lib "eagle-import") (part "C_CAP_1206"))
    )
    (comp (ref "C12")
      (value "C_CAP_1206")
      (footprint "eagle-import:C_1206")
      (libsource (lib "eagle-import") (part "C_CAP_1206"))
    )
    (comp (ref "C13")
      (value "C_CAP_1206")
      (footprint "eagle-import:C_1206")
      (libsource (lib "eagle-import") (part "C_CAP_1206"))
    )
    (comp (ref "C16")
      (value "C_CAP_1206")
      (footprint "eagle-import:C_1206")
      (libsource (lib "eagle-import") (part "C_CAP_1206"))
    )
    (comp (ref "C51")
      (value "C_CAP_1206")
      (footprint "eagle-import:C_1206")
      (libsource (lib "eagle-import") (part "C_CAP_1206"))
    )
    (comp (ref "J1")
      (value "J_MC32857")
      (footprint "eagle-import:J_TOGGLE")
      (libsource (lib "eagle-import") (part "J_MC32857"))
    )
    (comp (ref "Q8")
      (value "Q_LDOHEATSINK")
      (footprint "eagle-import:TO220_6025DG")
      (libsource (lib "eagle-import") (part "Q_LDOHEATSINK"))
    )
    (comp (ref "Q9")
      (value "Q_LTC490")
      (footprint "eagle-import:DIP8")
      (libsource (lib "eagle-import") (part "Q_LTC490"))
    )
    (comp (ref "R1")
      (value "R_RES_1206")
      (footprint "eagle-import:R_1206")
      (libsource (lib "eagle-import") (part "R_RES_1206"))
    )
    (comp (ref "R6")
      (value "R_RES_1206")
      (footprint "eagle-import:R_1206")
      (libsource (lib "eagle-import") (part "R_RES_1206"))
    )
    (comp (ref "R8")
      (value "R_RES_1206")
      (footprint "eagle-import:R_1206")
      (libsource (lib "eagle-import") (part "R_RES_1206"))
    )
    (comp (ref "U$13")
      (value "Q_LM35")
      (footprint "eagle-import:TO-92-3")
      (libsource (lib "eagle-import") (part "Q_LM35"))
    )
    (comp (ref "U$57")
      (value "Q_ATMEGA328P")
      (footprint "eagle-import:DIP28")
      (libsource (lib "eagle-import") (part "Q_ATMEGA328P"))
    )
    (comp (ref "U$64")
      (value "RJ45")
      (footprint "eagle-import:RJ45-CAT5E")
      (libsource (lib "eagle-import") (part "RJ45"))
    )
    (comp (ref "X1")
      (value "HC49S")
      (footprint "eagle-import:HC-49")
      (libsource (lib "eagle-import") (part "X_HC49SCRYSTAL"))
    )
    (comp (ref "C30")
      (value "C_CAP_1206")
      (footprint "eagle-import:C_1206")
      (libsource (lib "eagle-import") (part "C_CAP_1206"))
    )
    (comp (ref "C31")
      (value "C_CAP_1206")
      (footprint "eagle-import:C_1206")
      (libsource (lib "eagle-import") (part "C_CAP_1206"))
    )
    (comp (ref "C32")
      (value "C_CAP_1206")
      (footprint "eagle-import:C_1206")
      (libsource (lib "eagle-import") (part "C_CAP_1206"))
    )
    (comp (ref "C33")
      (value "C_CAP_1206")
      (footprint "eagle-import:C_1206")
      (libsource (lib "eagle-import") (part "C_CAP_1206"))
    )
    (comp (ref "C34")
      (value "C_CAP_1206")
      (footprint "eagle-import:C_1206")
      (libsource (lib "eagle-import") (part "C_CAP_1206"))
    )
    (comp (ref "C35")
      (value "C_CAP_1206")
      (footprint "eagle-import:C_1206")
      (libsource (lib "eagle-import") (part "C_CAP_1206"))
    )
    (comp (ref "C36")
      (value "C_CAP_1206")
      (footprint "eagle-import:C_1206")
      (libsource (lib "eagle-import") (part "C_CAP_1206"))
    )
    (comp (ref "C37")
      (value "C_CAP_1206")
      (footprint "eagle-import:C_1206")
      (libsource (lib "eagle-import") (part "C_CAP_1206"))
    )
    (comp (ref "C38")
      (value "C_CAP_1206")
      (footprint "eagle-import:C_1206")
      (libsource (lib "eagle-import") (part "C_CAP_1206"))
    )
    (comp (ref "C39")
      (value "C_CAP_1206")
      (footprint "eagle-import:C_1206")
      (libsource (lib "eagle-import") (part "C_CAP_1206"))
    )
    (comp (ref "C40")
      (value "C_CAP_1206")
      (footprint "eagle-import:C_1206")
      (libsource (lib "eagle-import") (part "C_CAP_1206"))
    )
    (comp (ref "C41")
      (value "C_CAP_1206")
      (footprint "eagle-import:C_1206")
      (libsource (lib "eagle-import") (part "C_CAP_1206"))
    )
    (comp (ref "C42")
      (value "C_CAP_1206")
      (footprint "eagle-import:C_1206")
      (libsource (lib "eagle-import") (part "C_CAP_1206"))
    )
    (comp (ref "C43")
      (value "C_CAP_1206")
      (footprint "eagle-import:C_1206")
      (libsource (lib "eagle-import") (part "C_CAP_1206"))
    )
    (comp (ref "C44")
      (value "C_CAP_1206")
      (footprint "eagle-import:C_1206")
      (libsource (lib "eagle-import") (part "C_CAP_1206"))
    )
    (comp (ref "C45")
      (value "C_CAP_1206")
      (footprint "eagle-import:C_1206")
      (libsource (lib "eagle-import") (part "C_CAP_1206"))
    )
    (comp (ref "C46")
      (value "C_CAP_1206")
      (footprint "eagle-import:C_1206")
      (libsource (lib "eagle-import") (part "C_CAP_1206"))
    )
    (comp (ref "C47")
      (value "C_CAP_1206")
      (footprint "eagle-import:C_1206")
      (libsource (lib "eagle-import") (part "C_CAP_1206"))
    )
    (comp (ref "Q1")
      (value "U_FDPF045N10A_TO-220F")
      (footprint "eagle-import:TO220F")
      (libsource (lib "eagle-import") (part "U_FDPF045N10A_TO-220F"))
    )
    (comp (ref "Q3")
      (value "U_FDPF045N10A_TO-220F")
      (footprint "eagle-import:TO220F")
      (libsource (lib "eagle-import") (part "U_FDPF045N10A_TO-220F"))
    )
    (comp (ref "Q4")
      (value "U_FDPF045N10A_TO-220F")
      (footprint "eagle-import:TO220F")
      (libsource (lib "eagle-import") (part "U_FDPF045N10A_TO-220F"))
    )
    (comp (ref "Q5")
      (value "U_FDPF045N10A_TO-220F")
      (footprint "eagle-import:TO220F")
      (libsource (lib "eagle-import") (part "U_FDPF045N10A_TO-220F"))
    )
    (comp (ref "Q6")
      (value "U_FDPF045N10A_TO-220F")
      (footprint "eagle-import:TO220F")
      (libsource (lib "eagle-import") (part "U_FDPF045N10A_TO-220F"))
    )
    (comp (ref "Q7")
      (value "U_FDPF045N10A_TO-220F")
      (footprint "eagle-import:TO220F")
      (libsource (lib "eagle-import") (part "U_FDPF045N10A_TO-220F"))
    )
    (comp (ref "R15")
      (value "R_RES_1206")
      (footprint "eagle-import:R_1206")
      (libsource (lib "eagle-import") (part "R_RES_1206"))
    )
    (comp (ref "R18")
      (value "R_RES_1206")
      (footprint "eagle-import:R_1206")
      (libsource (lib "eagle-import") (part "R_RES_1206"))
    )
    (comp (ref "R20")
      (value "R_RES_1206")
      (footprint "eagle-import:R_1206")
      (libsource (lib "eagle-import") (part "R_RES_1206"))
    )
    (comp (ref "R21")
      (value "R_RES_1206")
      (footprint "eagle-import:R_1206")
      (libsource (lib "eagle-import") (part "R_RES_1206"))
    )
    (comp (ref "R22")
      (value "R_RES_1206")
      (footprint "eagle-import:R_1206")
      (libsource (lib "eagle-import") (part "R_RES_1206"))
    )
    (comp (ref "R23")
      (value "R_RES_1206")
      (footprint "eagle-import:R_1206")
      (libsource (lib "eagle-import") (part "R_RES_1206"))
    )
    (comp (ref "U$11")
      (value "Q_MIC5021")
      (footprint "eagle-import:DIP8")
      (libsource (lib "eagle-import") (part "Q_MIC5021"))
    )
    (comp (ref "U$14")
      (value "J_1546074-2")
      (footprint "eagle-import:THERM_BLOCK_2")
      (libsource (lib "eagle-import") (part "J_1546074-2"))
    )
    (comp (ref "U$23")
      (value "Q_MIC5021")
      (footprint "eagle-import:DIP8")
      (libsource (lib "eagle-import") (part "Q_MIC5021"))
    )
    (comp (ref "U$26")
      (value "J_1546074-2")
      (footprint "eagle-import:THERM_BLOCK_2")
      (libsource (lib "eagle-import") (part "J_1546074-2"))
    )
    (comp (ref "U$27")
      (value "Q_MIC5021")
      (footprint "eagle-import:DIP8")
      (libsource (lib "eagle-import") (part "Q_MIC5021"))
    )
    (comp (ref "U$31")
      (value "J_1546074-2")
      (footprint "eagle-import:THERM_BLOCK_2")
      (libsource (lib "eagle-import") (part "J_1546074-2"))
    )
    (comp (ref "U$32")
      (value "Q_MIC5021")
      (footprint "eagle-import:DIP8")
      (libsource (lib "eagle-import") (part "Q_MIC5021"))
    )
    (comp (ref "U$36")
      (value "J_1546074-2")
      (footprint "eagle-import:THERM_BLOCK_2")
      (libsource (lib "eagle-import") (part "J_1546074-2"))
    )
    (comp (ref "U$37")
      (value "Q_MIC5021")
      (footprint "eagle-import:DIP8")
      (libsource (lib "eagle-import") (part "Q_MIC5021"))
    )
    (comp (ref "U$40")
      (value "J_1546074-2")
      (footprint "eagle-import:THERM_BLOCK_2")
      (libsource (lib "eagle-import") (part "J_1546074-2"))
    )
    (comp (ref "U$41")
      (value "Q_MIC5021")
      (footprint "eagle-import:DIP8")
      (libsource (lib "eagle-import") (part "Q_MIC5021"))
    )
    (comp (ref "U$44")
      (value "J_1546074-2")
      (footprint "eagle-import:THERM_BLOCK_2")
      (libsource (lib "eagle-import") (part "J_1546074-2"))
    )
    (comp (ref "U$45")
      (value "R_2512")
      (footprint "eagle-import:R_2512")
      (libsource (lib "eagle-import") (part "R_2512"))
    )
    (comp (ref "U$46")
      (value "R_2512")
      (footprint "eagle-import:R_2512")
      (libsource (lib "eagle-import") (part "R_2512"))
    )
    (comp (ref "U$47")
      (value "R_2512")
      (footprint "eagle-import:R_2512")
      (libsource (lib "eagle-import") (part "R_2512"))
    )
    (comp (ref "U$48")
      (value "R_2512")
      (footprint "eagle-import:R_2512")
      (libsource (lib "eagle-import") (part "R_2512"))
    )
    (comp (ref "U$49")
      (value "R_2512")
      (footprint "eagle-import:R_2512")
      (libsource (lib "eagle-import") (part "R_2512"))
    )
    (comp (ref "U$50")
      (value "R_2512")
      (footprint "eagle-import:R_2512")
      (libsource (lib "eagle-import") (part "R_2512"))
    )
    (comp (ref "C48")
      (value "C_CAP_1206")
      (footprint "eagle-import:C_1206")
      (libsource (lib "eagle-import") (part "C_CAP_1206"))
    )
    (comp (ref "C49")
      (value "C_CAP_1206")
      (footprint "eagle-import:C_1206")
      (libsource (lib "eagle-import") (part "C_CAP_1206"))
    )
    (comp (ref "C50")
      (value "C_CAP_1206")
      (footprint "eagle-import:C_1206")
      (libsource (lib "eagle-import") (part "C_CAP_1206"))
    )
    (comp (ref "Q15")
      (value "U_FDPF045N10A_TO-220F")
      (footprint "eagle-import:TO220F")
      (libsource (lib "eagle-import") (part "U_FDPF045N10A_TO-220F"))
    )
    (comp (ref "R24")
      (value "R_RES_1206")
      (footprint "eagle-import:R_1206")
      (libsource (lib "eagle-import") (part "R_RES_1206"))
    )
    (comp (ref "U$70")
      (value "Q_MIC5021")
      (footprint "eagle-import:DIP8")
      (libsource (lib "eagle-import") (part "Q_MIC5021"))
    )
    (comp (ref "U$72")
      (value "J_1546074-2")
      (footprint "eagle-import:THERM_BLOCK_2")
      (libsource (lib "eagle-import") (part "J_1546074-2"))
    )
    (comp (ref "U$73")
      (value "R_2512")
      (footprint "eagle-import:R_2512")
      (libsource (lib "eagle-import") (part "R_2512"))
    )
  )
  (nets
    (net (code "1") (name "GND") (class "Default")
      (node (ref "C1") (pin "1") (pinfunction "1_1") (pintype "passive"))
      (node (ref "C10") (pin "1") (pinfunction "1_1") (pintype "passive"))
      (node (ref "C11") (pin "2") (pinfunction "2_2") (pintype "passive"))
      (node (ref "C12") (pin "1") (pinfunction "1_1") (pintype "passive"))
      (node (ref "C13") (pin "2") (pinfunction "2_2") (pintype "passive"))
      (node (ref "C14") (pin "-") (pinfunction "-_-") (pintype "passive"))
      (node (ref "C15") (pin "-") (pinfunction "-_-") (pintype "passive"))
      (node (ref "C16") (pin "2") (pinfunction "2_2") (pintype "passive"))
      (node (ref "C17") (pin "-") (pinfunction "-_-") (pintype "passive"))
      (node (ref "C18") (pin "2") (pinfunction "2_2") (pintype "passive"))
      (node (ref "C19") (pin "1") (pinfunction "1_1") (pintype "passive"))
      (node (ref "C2") (pin "1") (pinfunction "1_1") (pintype "passive"))
      (node (ref "C21") (pin "1") (pinfunction "1_1") (pintype "passive"))
      (node (ref "C22") (pin "-") (pinfunction "-_-") (pintype "passive"))
      (node (ref "C23") (pin "2") (pinfunction "2_2") (pintype "passive"))
      (node (ref "C24") (pin "1") (pinfunction "1_1") (pintype "passive"))
      (node (ref "C25") (pin "2") (pinfunction "2_2") (pintype "passive"))
      (node (ref "C26") (pin "-") (pinfunction "-_-") (pintype "passive"))
      (node (ref "C27") (pin "2") (pinfunction "2_2") (pintype "passive"))
      (node (ref "C28") (pin "1") (pinfunction "1_1") (pintype "passive"))
      (node (ref "C29") (pin "1") (pinfunction "1_1") (pintype "passive"))
      (node (ref "C3") (pin "1") (pinfunction "1_1") (pintype "passive"))
      (node (ref "C36") (pin "2") (pinfunction "2_2") (pintype "passive"))
      (node (ref "C37") (pin "2") (pinfunction "2_2") (pintype "passive"))
      (node (ref "C38") (pin "2") (pinfunction "2_2") (pintype "passive"))
      (node (ref "C39") (pin "2") (pinfunction "2_2") (pintype "passive"))
      (node (ref "C4") (pin "1") (pinfunction "1_1") (pintype "passive"))
      (node (ref "C40") (pin "2") (pinfunction "2_2") (pintype "passive"))
      (node (ref "C41") (pin "2") (pinfunction "2_2") (pintype "passive"))
      (node (ref "C42") (pin "2") (pinfunction "2_2") (pintype "passive"))
      (node (ref "C43") (pin "2") (pinfunction "2_2") (pintype "passive"))
      (node (ref "C44") (pin "2") (pinfunction "2_2") (pintype "passive"))
      (node (ref "C45") (pin "2") (pinfunction "2_2") (pintype "passive"))
      (node (ref "C46") (pin "2") (pinfunction "2_2") (pintype "passive"))
      (node (ref "C47") (pin "2") (pinfunction "2_2") (pintype "passive"))
      (node (ref "C49") (pin "2") (pinfunction "2_2") (pintype "passive"))
      (node (ref "C5") (pin "1") (pinfunction "1_1") (pintype "passive"))
      (node (ref "C50") (pin "2") (pinfunction "2_2") (pintype "passive"))
      (node (ref "C51") (pin "1") (pinfunction "1_1") (pintype "passive"))
      (node (ref "C52") (pin "2") (pinfunction "2_2") (pintype "passive"))
      (node (ref "C53") (pin "2") (pinfunction "2_2") (pintype "passive"))
      (node (ref "C54") (pin "2") (pinfunction "2_2") (pintype "passive"))
      (node (ref "C56") (pin "-") (pinfunction "-_-") (pintype "passive"))
      (node (ref "C57") (pin "2") (pinfunction "2_2") (pintype "passive"))
      (node (ref "C58") (pin "P$2") (pinfunction "-_P$2") (pintype "passive"))
      (node (ref "C59") (pin "P$2") (pinfunction "-_P$2") (pintype "passive"))
      (node (ref "C6") (pin "1") (pinfunction "1_1") (pintype "passive"))
      (node (ref "C60") (pin "P$2") (pinfunction "-_P$2") (pintype "passive"))
      (node (ref "C61") (pin "P$2") (pinfunction "-_P$2") (pintype "passive"))
      (node (ref "C62") (pin "P$2") (pinfunction "-_P$2") (pintype "passive"))
      (node (ref "C63") (pin "P$2") (pinfunction "-_P$2") (pintype "passive"))
      (node (ref "C64") (pin "P$2") (pinfunction "-_P$2") (pintype "passive"))
      (node (ref "C65") (pin "P$2") (pinfunction "-_P$2") (pintype "passive"))
      (node (ref "C66") (pin "P$2") (pinfunction "-_P$2") (pintype "passive"))
      (node (ref "C67") (pin "P$2") (pinfunction "-_P$2") (pintype "passive"))
      (node (ref "C68") (pin "2") (pinfunction "2_2") (pintype "passive"))
      (node (ref "C69") (pin "2") (pinfunction "2_2") (pintype "passive"))
      (node (ref "C7") (pin "2") (pinfunction "2_2") (pintype "passive"))
      (node (ref "C70") (pin "2") (pinfunction "2_2") (pintype "passive"))
      (node (ref "C71") (pin "2") (pinfunction "2_2") (pintype "passive"))
      (node (ref "C72") (pin "2") (pinfunction "2_2") (pintype "passive"))
      (node (ref "C73") (pin "2") (pinfunction "2_2") (pintype "passive"))
      (node (ref "C74") (pin "2") (pinfunction "2_2") (pintype "passive"))
      (node (ref "C8") (pin "2") (pinfunction "2_2") (pintype "passive"))
      (node (ref "C9") (pin "1") (pinfunction "1_1") (pintype "passive"))
      (node (ref "D1") (pin "A") (pinfunction "A_A") (pintype "passive"))
      (node (ref "D10") (pin "A") (pinfunction "A_A") (pintype "passive"))
      (node (ref "D2") (pin "A") (pinfunction "A_A") (pintype "passive"))
      (node (ref "D3") (pin "A") (pinfunction "A_A") (pintype "passive"))
      (node (ref "D4") (pin "A") (pinfunction "A_A") (pintype "passive"))
      (node (ref "D5") (pin "A") (pinfunction "A_A") (pintype "passive"))
      (node (ref "D6") (pin "A") (pinfunction "A_A") (pintype "passive"))
      (node (ref "D7") (pin "A") (pinfunction "A_A") (pintype "passive"))
      (node (ref "J1") (pin "P$1") (pinfunction "1_P$1") (pintype "bidirectional"))
      (node (ref "J2") (pin "PIN2-1") (pinfunction "2-1_PIN2-1") (pintype "bidirectional"))
      (node (ref "J2") (pin "PIN2-2") (pinfunction "2-2_PIN2-2") (pintype "bidirectional"))
      (node (ref "J3") (pin "P$2") (pinfunction "P$2_P$2") (pintype "bidirectional"))
      (node (ref "J4") (pin "P$2") (pinfunction "P$2_P$2") (pintype "bidirectional"))
      (node (ref "J5") (pin "P$2") (pinfunction "P$2_P$2") (pintype "bidirectional"))
      (node (ref "J6") (pin "P$2") (pinfunction "P$2_P$2") (pintype "bidirectional"))
      (node (ref "J7") (pin "P$2") (pinfunction "P$2_P$2") (pintype "bidirectional"))
      (node (ref "J8") (pin "P$2") (pinfunction "P$2_P$2") (pintype "bidirectional"))
      (node (ref "JOLTEON-12V-1") (pin "1") (pinfunction "GND_1") (pintype "bidirectional"))
      (node (ref "JOLTEON-12V-1") (pin "7") (pinfunction "GND1_7") (pintype "bidirectional"))
      (node (ref "MAGNEMITE-12V-2") (pin "1") (pinfunction "GND_1") (pintype "bidirectional"))
      (node (ref "MAGNEMITE-12V-2") (pin "7") (pinfunction "GND1_7") (pintype "bidirectional"))
      (node (ref "N1") (pin "1-7") (pinfunction "7-DC--_1-7") (pintype "bidirectional"))
      (node (ref "N1") (pin "1-8") (pinfunction "8-DC-_1-8") (pintype "bidirectional"))
      (node (ref "N1") (pin "2-7") (pinfunction "7-DC--_2-7") (pintype "bidirectional"))
      (node (ref "N1") (pin "2-8") (pinfunction "8-DC-_2-8") (pintype "bidirectional"))
      (node (ref "N2") (pin "1-7") (pinfunction "7-DC--_1-7") (pintype "bidirectional"))
      (node (ref "N2") (pin "1-8") (pinfunction "8-DC-_1-8") (pintype "bidirectional"))
      (node (ref "N2") (pin "2-7") (pinfunction "7-DC--_2-7") (pintype "bidirectional"))
      (node (ref "N2") (pin "2-8") (pinfunction "8-DC-_2-8") (pintype "bidirectional"))
      (node (ref "N3") (pin "1-7") (pinfunction "7-DC--_1-7") (pintype "bidirectional"))
      (node (ref "N3") (pin "1-8") (pinfunction "8-DC-_1-8") (pintype "bidirectional"))
      (node (ref "N3") (pin "2-7") (pinfunction "7-DC--_2-7") (pintype "bidirectional"))
      (node (ref "N3") (pin "2-8") (pinfunction "8-DC-_2-8") (pintype "bidirectional"))
      (node (ref "N4") (pin "1-7") (pinfunction "7-DC--_1-7") (pintype "bidirectional"))
      (node (ref "N4") (pin "1-8") (pinfunction "8-DC-_1-8") (pintype "bidirectional"))
      (node (ref "N4") (pin "2-7") (pinfunction "7-DC--_2-7") (pintype "bidirectional"))
      (node (ref "N4") (pin "2-8") (pinfunction "8-DC-_2-8") (pintype "bidirectional"))
      (node (ref "N5") (pin "1-7") (pinfunction "7-DC--_1-7") (pintype "bidirectional"))
      (node (ref "N5") (pin "1-8") (pinfunction "8-DC-_1-8") (pintype "bidirectional"))
      (node (ref "N5") (pin "2-7") (pinfunction "7-DC--_2-7") (pintype "bidirectional"))
      (node (ref "N5") (pin "2-8") (pinfunction "8-DC-_2-8") (pintype "bidirectional"))
      (node (ref "N6") (pin "1-7") (pinfunction "7-DC--_1-7") (pintype "bidirectional"))
      (node (ref "N6") (pin "1-8") (pinfunction "8-DC-_1-8") (pintype "bidirectional"))
      (node (ref "N6") (pin "2-7") (pinfunction "7-DC--_2-7") (pintype "bidirectional"))
      (node (ref "N6") (pin "2-8") (pinfunction "8-DC-_2-8") (pintype "bidirectional"))
      (node (ref "N7") (pin "1-7") (pinfunction "7-DC--_1-7") (pintype "bidirectional"))
      (node (ref "N7") (pin "1-8") (pinfunction "8-DC-_1-8") (pintype "bidirectional"))
      (node (ref "N7") (pin "2-7") (pinfunction "7-DC--_2-7") (pintype "bidirectional"))
      (node (ref "N7") (pin "2-8") (pinfunction "8-DC-_2-8") (pintype "bidirectional"))
      (node (ref "N8") (pin "1-7") (pinfunction "7-DC--_1-7") (pintype "bidirectional"))
      (node (ref "N8") (pin "1-8") (pinfunction "8-DC-_1-8") (pintype "bidirectional"))
      (node (ref "N8") (pin "2-7") (pinfunction "7-DC--_2-7") (pintype "bidirectional"))
      (node (ref "N8") (pin "2-8") (pinfunction "8-DC-_2-8") (pintype "bidirectional"))
      (node (ref "PICKACHU-5V") (pin "1") (pinfunction "GND_1") (pintype "bidirectional"))
      (node (ref "PICKACHU-5V") (pin "7") (pinfunction "GND1_7") (pintype "bidirectional"))
      (node (ref "Q10") (pin "1") (pinfunction "S_1") (pintype "bidirectional"))
      (node (ref "Q11") (pin "1") (pinfunction "S_1") (pintype "bidirectional"))
      (node (ref "Q12") (pin "1") (pinfunction "S_1") (pintype "bidirectional"))
      (node (ref "Q14") (pin "1") (pinfunction "S_1") (pintype "bidirectional"))
      (node (ref "Q8") (pin "2") (pinfunction "GND_2") (pintype "bidirectional"))
      (node (ref "Q9") (pin "4") (pinfunction "GND_4") (pintype "bidirectional"))
      (node (ref "R10") (pin "1") (pinfunction "1_1") (pintype "passive"))
      (node (ref "R11") (pin "1") (pinfunction "1_1") (pintype "passive"))
      (node (ref "R12") (pin "1") (pinfunction "1_1") (pintype "passive"))
      (node (ref "R2") (pin "1") (pinfunction "1_1") (pintype "passive"))
      (node (ref "R28") (pin "1") (pinfunction "1_1") (pintype "passive"))
      (node (ref "R3") (pin "1") (pinfunction "1_1") (pintype "passive"))
      (node (ref "R30") (pin "1") (pinfunction "1_1") (pintype "passive"))
      (node (ref "R31") (pin "1") (pinfunction "1_1") (pintype "passive"))
      (node (ref "R4") (pin "1") (pinfunction "1_1") (pintype "passive"))
      (node (ref "R5") (pin "1") (pinfunction "1_1") (pintype "passive"))
      (node (ref "RAICHU-5V-CRIT") (pin "1") (pinfunction "GND_1") (pintype "bidirectional"))
      (node (ref "RAICHU-5V-CRIT") (pin "7") (pinfunction "GND1_7") (pintype "bidirectional"))
      (node (ref "U$11") (pin "4") (pinfunction "GND_4") (pintype "bidirectional"))
      (node (ref "U$13") (pin "1") (pinfunction "GND_1") (pintype "bidirectional"))
      (node (ref "U$14") (pin "P$2") (pinfunction "P$2_P$2") (pintype "bidirectional"))
      (node (ref "U$17") (pin "4") (pinfunction "GND_4") (pintype "bidirectional"))
      (node (ref "U$23") (pin "4") (pinfunction "GND_4") (pintype "bidirectional"))
      (node (ref "U$26") (pin "P$2") (pinfunction "P$2_P$2") (pintype "bidirectional"))
      (node (ref "U$27") (pin "4") (pinfunction "GND_4") (pintype "bidirectional"))
      (node (ref "U$31") (pin "P$2") (pinfunction "P$2_P$2") (pintype "bidirectional"))
      (node (ref "U$32") (pin "4") (pinfunction "GND_4") (pintype "bidirectional"))
      (node (ref "U$36") (pin "P$2") (pinfunction "P$2_P$2") (pintype "bidirectional"))
      (node (ref "U$37") (pin "4") (pinfunction "GND_4") (pintype "bidirectional"))
      (node (ref "U$40") (pin "P$2") (pinfunction "P$2_P$2") (pintype "bidirectional"))
      (node (ref "U$41") (pin "4") (pinfunction "GND_4") (pintype "bidirectional"))
      (node (ref "U$44") (pin "P$2") (pinfunction "P$2_P$2") (pintype "bidirectional"))
      (node (ref "U$52") (pin "P$2") (pinfunction "P$2_P$2") (pintype "bidirectional"))
      (node (ref "U$53") (pin "P$2") (pinfunction "P$2_P$2") (pintype "bidirectional"))
      (node (ref "U$54") (pin "P$2") (pinfunction "P$2_P$2") (pintype "bidirectional"))
      (node (ref "U$55") (pin "P$2") (pinfunction "P$2_P$2") (pintype "bidirectional"))
      (node (ref "U$57") (pin "22") (pinfunction "GND1_22") (pintype "bidirectional"))
      (node (ref "U$57") (pin "8") (pinfunction "GND_8") (pintype "bidirectional"))
      (node (ref "U$64") (pin "7") (pinfunction "7-DC--_7") (pintype "bidirectional"))
      (node (ref "U$64") (pin "8") (pinfunction "8-DC-_8") (pintype "bidirectional"))
      (node (ref "U$70") (pin "4") (pinfunction "GND_4") (pintype "bidirectional"))
      (node (ref "U$72") (pin "P$2") (pinfunction "P$2_P$2") (pintype "bidirectional"))
      (node (ref "ZAPDOS-20V") (pin "1") (pinfunction "GND_1") (pintype "bidirectional"))
      (node (ref "ZAPDOS-20V") (pin "7") (pinfunction "GND1_7") (pintype "bidirectional"))
    )
    (net (code "2") (name "M_IMAIN") (class "Default")
      (node (ref "R11") (pin "2") (pinfunction "2_2") (pintype "passive"))
      (node (ref "U$16") (pin "3") (pinfunction "OUT_3") (pintype "bidirectional"))
      (node (ref "U$57") (pin "28") (pinfunction "PC5_28") (pintype "bidirectional"))
    )
    (net (code "3") (name "M_V5-2") (class "Default")
      (node (ref "C52") (pin "1") (pinfunction "1_1") (pintype "passive"))
      (node (ref "R26") (pin "1") (pinfunction "1_1") (pintype "passive"))
      (node (ref "R28") (pin "2") (pinfunction "2_2") (pintype "passive"))
      (node (ref "U$57") (pin "24") (pinfunction "PC1_24") (pintype "bidirectional"))
    )
    (net (code "4") (name "M_V12-1") (class "Default")
      (node (ref "C53") (pin "1") (pinfunction "1_1") (pintype "passive"))
      (node (ref "R27") (pin "1") (pinfunction "1_1") (pintype "passive"))
      (node (ref "R30") (pin "2") (pinfunction "2_2") (pintype "passive"))
      (node (ref "U$57") (pin "25") (pinfunction "PC2_25") (pintype "bidirectional"))
    )
    (net (code "5") (name "M_V12-2") (class "Default")
      (node (ref "C54") (pin "1") (pinfunction "1_1") (pintype "passive"))
      (node (ref "R29") (pin "1") (pinfunction "1_1") (pintype "passive"))
      (node (ref "R31") (pin "2") (pinfunction "2_2") (pintype "passive"))
      (node (ref "U$57") (pin "26") (pinfunction "PC3_26") (pintype "bidirectional"))
    )
    (net (code "6") (name "M_VMAIN") (class "Default")
      (node (ref "C25") (pin "1") (pinfunction "1_1") (pintype "passive"))
      (node (ref "R10") (pin "2") (pinfunction "2_2") (pintype "passive"))
      (node (ref "R9") (pin "1") (pinfunction "1_1") (pintype "passive"))
      (node (ref "U$57") (pin "27") (pinfunction "PC4_27") (pintype "bidirectional"))
    )
    (net (code "7") (name "Net-(D1-K)") (class "Default")
      (node (ref "C18") (pin "1") (pinfunction "1_1") (pintype "passive"))
      (node (ref "C73") (pin "1") (pinfunction "1_1") (pintype "passive"))
      (node (ref "D1") (pin "C") (pinfunction "K_C") (pintype "passive"))
      (node (ref "J6") (pin "P$1") (pinfunction "P$1_P$1") (pintype "bidirectional"))
      (node (ref "J7") (pin "P$1") (pinfunction "P$1_P$1") (pintype "bidirectional"))
      (node (ref "J8") (pin "P$1") (pinfunction "P$1_P$1") (pintype "bidirectional"))
      (node (ref "L6") (pin "5") (pinfunction "5_5") (pintype "bidirectional"))
      (node (ref "L6") (pin "6") (pinfunction "6_6") (pintype "bidirectional"))
      (node (ref "L6") (pin "7") (pinfunction "7_7") (pintype "bidirectional"))
      (node (ref "L6") (pin "8") (pinfunction "8_8") (pintype "bidirectional"))
    )
    (net (code "8") (name "Net-(D2-K)") (class "Default")
      (node (ref "C23") (pin "1") (pinfunction "1_1") (pintype "passive"))
      (node (ref "C74") (pin "1") (pinfunction "1_1") (pintype "passive"))
      (node (ref "D2") (pin "C") (pinfunction "K_C") (pintype "passive"))
      (node (ref "J3") (pin "P$1") (pinfunction "P$1_P$1") (pintype "bidirectional"))
      (node (ref "J4") (pin "P$1") (pinfunction "P$1_P$1") (pintype "bidirectional"))
      (node (ref "J5") (pin "P$1") (pinfunction "P$1_P$1") (pintype "bidirectional"))
      (node (ref "L8") (pin "5") (pinfunction "5_5") (pintype "bidirectional"))
      (node (ref "L8") (pin "6") (pinfunction "6_6") (pintype "bidirectional"))
      (node (ref "L8") (pin "7") (pinfunction "7_7") (pintype "bidirectional"))
      (node (ref "L8") (pin "8") (pinfunction "8_8") (pintype "bidirectional"))
    )
    (net (code "9") (name "Net-(D3-K)") (class "Default")
      (node (ref "C72") (pin "1") (pinfunction "1_1") (pintype "passive"))
      (node (ref "C8") (pin "1") (pinfunction "1_1") (pintype "passive"))
      (node (ref "D3") (pin "C") (pinfunction "K_C") (pintype "passive"))
      (node (ref "L4") (pin "5") (pinfunction "5_5") (pintype "bidirectional"))
      (node (ref "L4") (pin "6") (pinfunction "6_6") (pintype "bidirectional"))
      (node (ref "L4") (pin "7") (pinfunction "7_7") (pintype "bidirectional"))
      (node (ref "L4") (pin "8") (pinfunction "8_8") (pintype "bidirectional"))
      (node (ref "U$52") (pin "P$1") (pinfunction "P$1_P$1") (pintype "bidirectional"))
      (node (ref "U$53") (pin "P$1") (pinfunction "P$1_P$1") (pintype "bidirectional"))
    )
    (net (code "10") (name "Net-(D7-K)") (class "Default")
      (node (ref "C7") (pin "1") (pinfunction "1_1") (pintype "passive"))
      (node (ref "C71") (pin "1") (pinfunction "1_1") (pintype "passive"))
      (node (ref "D7") (pin "C") (pinfunction "K_C") (pintype "passive"))
      (node (ref "L3") (pin "5") (pinfunction "5_5") (pintype "bidirectional"))
      (node (ref "L3") (pin "6") (pinfunction "6_6") (pintype "bidirectional"))
      (node (ref "L3") (pin "7") (pinfunction "7_7") (pintype "bidirectional"))
      (node (ref "L3") (pin "8") (pinfunction "8_8") (pintype "bidirectional"))
      (node (ref "U$54") (pin "P$1") (pinfunction "P$1_P$1") (pintype "bidirectional"))
      (node (ref "U$55") (pin "P$1") (pinfunction "P$1_P$1") (pintype "bidirectional"))
    )
    (net (code "11") (name "Net-(J1-2)") (class "Default")
      (node (ref "J1") (pin "P$2") (pinfunction "2_P$2") (pintype "bidirectional"))
      (node (ref "R1") (pin "1") (pinfunction "1_1") (pintype "passive"))
      (node (ref "U$57") (pin "1") (pinfunction "PC6_1") (pintype "bidirectional"))
    )
    (net (code "12") (name "Net-(JOLTEON-12V-1-ADJUST)") (class "Default")
      (node (ref "JOLTEON-12V-1") (pin "4") (pinfunction "ADJUST_4") (pintype "bidirectional"))
      (node (ref "R5") (pin "2") (pinfunction "2_2") (pintype "passive"))
    )
    (net (code "13") (name "Net-(JOLTEON-12V-1-INHIBIT)") (class "Default")
      (node (ref "JOLTEON-12V-1") (pin "3") (pinfunction "INHIBIT_3") (pintype "bidirectional"))
      (node (ref "Q10") (pin "3") (pinfunction "D_3") (pintype "bidirectional"))
    )
    (net (code "14") (name "Net-(JOLTEON-12V-1-SENSE)") (class "Default")
      (node (ref "C22") (pin "+") (pinfunction "+_+") (pintype "passive"))
      (node (ref "JOLTEON-12V-1") (pin "5") (pinfunction "SENSE_5") (pintype "bidirectional"))
      (node (ref "JOLTEON-12V-1") (pin "6") (pinfunction "VOUT_6") (pintype "bidirectional"))
      (node (ref "L8") (pin "1") (pinfunction "1_1") (pintype "bidirectional"))
      (node (ref "L8") (pin "2") (pinfunction "2_2") (pintype "bidirectional"))
      (node (ref "L8") (pin "3") (pinfunction "3_3") (pintype "bidirectional"))
      (node (ref "L8") (pin "4") (pinfunction "4_4") (pintype "bidirectional"))
      (node (ref "R27") (pin "2") (pinfunction "2_2") (pintype "passive"))
    )
    (net (code "15") (name "Net-(JOLTEON-12V-1-VIN)") (class "Default")
      (node (ref "C2") (pin "2") (pinfunction "2_2") (pintype "passive"))
      (node (ref "JOLTEON-12V-1") (pin "2") (pinfunction "VIN_2") (pintype "bidirectional"))
      (node (ref "L7") (pin "5") (pinfunction "5_5") (pintype "bidirectional"))
      (node (ref "L7") (pin "6") (pinfunction "6_6") (pintype "bidirectional"))
      (node (ref "L7") (pin "7") (pinfunction "7_7") (pintype "bidirectional"))
      (node (ref "L7") (pin "8") (pinfunction "8_8") (pintype "bidirectional"))
    )
    (net (code "16") (name "Net-(MAGNEMITE-12V-2-ADJUST)") (class "Default")
      (node (ref "MAGNEMITE-12V-2") (pin "4") (pinfunction "ADJUST_4") (pintype "bidirectional"))
      (node (ref "R4") (pin "2") (pinfunction "2_2") (pintype "passive"))
    )
    (net (code "17") (name "Net-(MAGNEMITE-12V-2-INHIBIT)") (class "Default")
      (node (ref "MAGNEMITE-12V-2") (pin "3") (pinfunction "INHIBIT_3") (pintype "bidirectional"))
      (node (ref "Q12") (pin "3") (pinfunction "D_3") (pintype "bidirectional"))
    )
    (net (code "18") (name "Net-(MAGNEMITE-12V-2-SENSE)") (class "Default")
      (node (ref "C26") (pin "+") (pinfunction "+_+") (pintype "passive"))
      (node (ref "L6") (pin "1") (pinfunction "1_1") (pintype "bidirectional"))
      (node (ref "L6") (pin "2") (pinfunction "2_2") (pintype "bidirectional"))
      (node (ref "L6") (pin "3") (pinfunction "3_3") (pintype "bidirectional"))
      (node (ref "L6") (pin "4") (pinfunction "4_4") (pintype "bidirectional"))
      (node (ref "MAGNEMITE-12V-2") (pin "5") (pinfunction "SENSE_5") (pintype "bidirectional"))
      (node (ref "MAGNEMITE-12V-2") (pin "6") (pinfunction "VOUT_6") (pintype "bidirectional"))
      (node (ref "R29") (pin "2") (pinfunction "2_2") (pintype "passive"))
    )
    (net (code "19") (name "Net-(MAGNEMITE-12V-2-VIN)") (class "Default")
      (node (ref "C1") (pin "2") (pinfunction "2_2") (pintype "passive"))
      (node (ref "L5") (pin "5") (pinfunction "5_5") (pintype "bidirectional"))
      (node (ref "L5") (pin "6") (pinfunction "6_6") (pintype "bidirectional"))
      (node (ref "L5") (pin "7") (pinfunction "7_7") (pintype "bidirectional"))
      (node (ref "L5") (pin "8") (pinfunction "8_8") (pintype "bidirectional"))
      (node (ref "MAGNEMITE-12V-2") (pin "2") (pinfunction "VIN_2") (pintype "bidirectional"))
    )
    (net (code "20") (name "Net-(N1A-1-TRANS+)") (class "Default")
      (node (ref "N1") (pin "1-1") (pinfunction "1-TRANS+_1-1") (pintype "bidirectional"))
      (node (ref "N1") (pin "2-1") (pinfunction "1-TRANS+_2-1") (pintype "bidirectional"))
    )
    (net (code "21") (name "Net-(N1A-2-TRANS-)") (class "Default")
      (node (ref "N1") (pin "1-2") (pinfunction "2-TRANS-_1-2") (pintype "bidirectional"))
      (node (ref "N1") (pin "2-2") (pinfunction "2-TRANS-_2-2") (pintype "bidirectional"))
    )
    (net (code "22") (name "Net-(N1A-3+RECEIVE+)") (class "Default")
      (node (ref "N1") (pin "1-3") (pinfunction "3+RECEIVE+_1-3") (pintype "bidirectional"))
      (node (ref "N1") (pin "2-3") (pinfunction "3+RECEIVE+_2-3") (pintype "bidirectional"))
    )
    (net (code "23") (name "Net-(N1A-6-RECEIVE-)") (class "Default")
      (node (ref "N1") (pin "1-6") (pinfunction "6-RECEIVE-_1-6") (pintype "bidirectional"))
      (node (ref "N1") (pin "2-6") (pinfunction "6-RECEIVE-_2-6") (pintype "bidirectional"))
    )
    (net (code "24") (name "Net-(N2A-1-TRANS+)") (class "Default")
      (node (ref "N2") (pin "1-1") (pinfunction "1-TRANS+_1-1") (pintype "bidirectional"))
      (node (ref "N2") (pin "2-1") (pinfunction "1-TRANS+_2-1") (pintype "bidirectional"))
    )
    (net (code "25") (name "Net-(N2A-2-TRANS-)") (class "Default")
      (node (ref "N2") (pin "1-2") (pinfunction "2-TRANS-_1-2") (pintype "bidirectional"))
      (node (ref "N2") (pin "2-2") (pinfunction "2-TRANS-_2-2") (pintype "bidirectional"))
    )
    (net (code "26") (name "Net-(N2A-3+RECEIVE+)") (class "Default")
      (node (ref "N2") (pin "1-3") (pinfunction "3+RECEIVE+_1-3") (pintype "bidirectional"))
      (node (ref "N2") (pin "2-3") (pinfunction "3+RECEIVE+_2-3") (pintype "bidirectional"))
    )
    (net (code "27") (name "Net-(N2A-6-RECEIVE-)") (class "Default")
      (node (ref "N2") (pin "1-6") (pinfunction "6-RECEIVE-_1-6") (pintype "bidirectional"))
      (node (ref "N2") (pin "2-6") (pinfunction "6-RECEIVE-_2-6") (pintype "bidirectional"))
    )
    (net (code "28") (name "Net-(N3A-1-TRANS+)") (class "Default")
      (node (ref "N3") (pin "1-1") (pinfunction "1-TRANS+_1-1") (pintype "bidirectional"))
      (node (ref "N3") (pin "2-1") (pinfunction "1-TRANS+_2-1") (pintype "bidirectional"))
    )
    (net (code "29") (name "Net-(N3A-2-TRANS-)") (class "Default")
      (node (ref "N3") (pin "1-2") (pinfunction "2-TRANS-_1-2") (pintype "bidirectional"))
      (node (ref "N3") (pin "2-2") (pinfunction "2-TRANS-_2-2") (pintype "bidirectional"))
    )
    (net (code "30") (name "Net-(N3A-3+RECEIVE+)") (class "Default")
      (node (ref "N3") (pin "1-3") (pinfunction "3+RECEIVE+_1-3") (pintype "bidirectional"))
      (node (ref "N3") (pin "2-3") (pinfunction "3+RECEIVE+_2-3") (pintype "bidirectional"))
    )
    (net (code "31") (name "Net-(N3A-6-RECEIVE-)") (class "Default")
      (node (ref "N3") (pin "1-6") (pinfunction "6-RECEIVE-_1-6") (pintype "bidirectional"))
      (node (ref "N3") (pin "2-6") (pinfunction "6-RECEIVE-_2-6") (pintype "bidirectional"))
    )
    (net (code "32") (name "Net-(N4A-1-TRANS+)") (class "Default")
      (node (ref "N4") (pin "1-1") (pinfunction "1-TRANS+_1-1") (pintype "bidirectional"))
      (node (ref "N4") (pin "2-1") (pinfunction "1-TRANS+_2-1") (pintype "bidirectional"))
    )
    (net (code "33") (name "Net-(N4A-2-TRANS-)") (class "Default")
      (node (ref "N4") (pin "1-2") (pinfunction "2-TRANS-_1-2") (pintype "bidirectional"))
      (node (ref "N4") (pin "2-2") (pinfunction "2-TRANS-_2-2") (pintype "bidirectional"))
    )
    (net (code "34") (name "Net-(N4A-3+RECEIVE+)") (class "Default")
      (node (ref "N4") (pin "1-3") (pinfunction "3+RECEIVE+_1-3") (pintype "bidirectional"))
      (node (ref "N4") (pin "2-3") (pinfunction "3+RECEIVE+_2-3") (pintype "bidirectional"))
    )
    (net (code "35") (name "Net-(N4A-6-RECEIVE-)") (class "Default")
      (node (ref "N4") (pin "1-6") (pinfunction "6-RECEIVE-_1-6") (pintype "bidirectional"))
      (node (ref "N4") (pin "2-6") (pinfunction "6-RECEIVE-_2-6") (pintype "bidirectional"))
    )
    (net (code "36") (name "Net-(N5A-1-TRANS+)") (class "Default")
      (node (ref "N5") (pin "1-1") (pinfunction "1-TRANS+_1-1") (pintype "bidirectional"))
      (node (ref "N5") (pin "2-1") (pinfunction "1-TRANS+_2-1") (pintype "bidirectional"))
    )
    (net (code "37") (name "Net-(N5A-2-TRANS-)") (class "Default")
      (node (ref "N5") (pin "1-2") (pinfunction "2-TRANS-_1-2") (pintype "bidirectional"))
      (node (ref "N5") (pin "2-2") (pinfunction "2-TRANS-_2-2") (pintype "bidirectional"))
    )
    (net (code "38") (name "Net-(N5A-3+RECEIVE+)") (class "Default")
      (node (ref "N5") (pin "1-3") (pinfunction "3+RECEIVE+_1-3") (pintype "bidirectional"))
      (node (ref "N5") (pin "2-3") (pinfunction "3+RECEIVE+_2-3") (pintype "bidirectional"))
    )
    (net (code "39") (name "Net-(N5A-6-RECEIVE-)") (class "Default")
      (node (ref "N5") (pin "1-6") (pinfunction "6-RECEIVE-_1-6") (pintype "bidirectional"))
      (node (ref "N5") (pin "2-6") (pinfunction "6-RECEIVE-_2-6") (pintype "bidirectional"))
    )
    (net (code "40") (name "Net-(N6A-1-TRANS+)") (class "Default")
      (node (ref "N6") (pin "1-1") (pinfunction "1-TRANS+_1-1") (pintype "bidirectional"))
      (node (ref "N6") (pin "2-1") (pinfunction "1-TRANS+_2-1") (pintype "bidirectional"))
    )
    (net (code "41") (name "Net-(N6A-2-TRANS-)") (class "Default")
      (node (ref "N6") (pin "1-2") (pinfunction "2-TRANS-_1-2") (pintype "bidirectional"))
      (node (ref "N6") (pin "2-2") (pinfunction "2-TRANS-_2-2") (pintype "bidirectional"))
    )
    (net (code "42") (name "Net-(N6A-3+RECEIVE+)") (class "Default")
      (node (ref "N6") (pin "1-3") (pinfunction "3+RECEIVE+_1-3") (pintype "bidirectional"))
      (node (ref "N6") (pin "2-3") (pinfunction "3+RECEIVE+_2-3") (pintype "bidirectional"))
    )
    (net (code "43") (name "Net-(N6A-6-RECEIVE-)") (class "Default")
      (node (ref "N6") (pin "1-6") (pinfunction "6-RECEIVE-_1-6") (pintype "bidirectional"))
      (node (ref "N6") (pin "2-6") (pinfunction "6-RECEIVE-_2-6") (pintype "bidirectional"))
    )
    (net (code "44") (name "Net-(N7A-1-TRANS+)") (class "Default")
      (node (ref "N7") (pin "1-1") (pinfunction "1-TRANS+_1-1") (pintype "bidirectional"))
      (node (ref "N7") (pin "2-1") (pinfunction "1-TRANS+_2-1") (pintype "bidirectional"))
    )
    (net (code "45") (name "Net-(N7A-2-TRANS-)") (class "Default")
      (node (ref "N7") (pin "1-2") (pinfunction "2-TRANS-_1-2") (pintype "bidirectional"))
      (node (ref "N7") (pin "2-2") (pinfunction "2-TRANS-_2-2") (pintype "bidirectional"))
    )
    (net (code "46") (name "Net-(N7A-3+RECEIVE+)") (class "Default")
      (node (ref "N7") (pin "1-3") (pinfunction "3+RECEIVE+_1-3") (pintype "bidirectional"))
      (node (ref "N7") (pin "2-3") (pinfunction "3+RECEIVE+_2-3") (pintype "bidirectional"))
    )
    (net (code "47") (name "Net-(N7A-6-RECEIVE-)") (class "Default")
      (node (ref "N7") (pin "1-6") (pinfunction "6-RECEIVE-_1-6") (pintype "bidirectional"))
      (node (ref "N7") (pin "2-6") (pinfunction "6-RECEIVE-_2-6") (pintype "bidirectional"))
    )
    (net (code "48") (name "Net-(N8A-1-TRANS+)") (class "Default")
      (node (ref "N8") (pin "1-1") (pinfunction "1-TRANS+_1-1") (pintype "bidirectional"))
      (node (ref "N8") (pin "2-1") (pinfunction "1-TRANS+_2-1") (pintype "bidirectional"))
    )
    (net (code "49") (name "Net-(N8A-2-TRANS-)") (class "Default")
      (node (ref "N8") (pin "1-2") (pinfunction "2-TRANS-_1-2") (pintype "bidirectional"))
      (node (ref "N8") (pin "2-2") (pinfunction "2-TRANS-_2-2") (pintype "bidirectional"))
    )
    (net (code "50") (name "Net-(N8A-3+RECEIVE+)") (class "Default")
      (node (ref "N8") (pin "1-3") (pinfunction "3+RECEIVE+_1-3") (pintype "bidirectional"))
      (node (ref "N8") (pin "2-3") (pinfunction "3+RECEIVE+_2-3") (pintype "bidirectional"))
    )
    (net (code "51") (name "Net-(N8A-6-RECEIVE-)") (class "Default")
      (node (ref "N8") (pin "1-6") (pinfunction "6-RECEIVE-_1-6") (pintype "bidirectional"))
      (node (ref "N8") (pin "2-6") (pinfunction "6-RECEIVE-_2-6") (pintype "bidirectional"))
    )
    (net (code "52") (name "Net-(PICKACHU-5V-ADJUST)") (class "Default")
      (node (ref "PICKACHU-5V") (pin "4") (pinfunction "ADJUST_4") (pintype "bidirectional"))
      (node (ref "R2") (pin "2") (pinfunction "2_2") (pintype "passive"))
    )
    (net (code "53") (name "Net-(PICKACHU-5V-INHIBIT)") (class "Default")
      (node (ref "PICKACHU-5V") (pin "3") (pinfunction "INHIBIT_3") (pintype "bidirectional"))
      (node (ref "Q14") (pin "3") (pinfunction "D_3") (pintype "bidirectional"))
    )
    (net (code "54") (name "Net-(PICKACHU-5V-SENSE)") (class "Default")
      (node (ref "C14") (pin "+") (pinfunction "+_+") (pintype "passive"))
      (node (ref "L3") (pin "1") (pinfunction "1_1") (pintype "bidirectional"))
      (node (ref "L3") (pin "2") (pinfunction "2_2") (pintype "bidirectional"))
      (node (ref "L3") (pin "3") (pinfunction "3_3") (pintype "bidirectional"))
      (node (ref "L3") (pin "4") (pinfunction "4_4") (pintype "bidirectional"))
      (node (ref "PICKACHU-5V") (pin "5") (pinfunction "SENSE_5") (pintype "bidirectional"))
      (node (ref "PICKACHU-5V") (pin "6") (pinfunction "VOUT_6") (pintype "bidirectional"))
      (node (ref "R26") (pin "2") (pinfunction "2_2") (pintype "passive"))
    )
    (net (code "55") (name "Net-(PICKACHU-5V-VIN)") (class "Default")
      (node (ref "C3") (pin "2") (pinfunction "2_2") (pintype "passive"))
      (node (ref "L2") (pin "5") (pinfunction "5_5") (pintype "bidirectional"))
      (node (ref "L2") (pin "6") (pinfunction "6_6") (pintype "bidirectional"))
      (node (ref "L2") (pin "7") (pinfunction "7_7") (pintype "bidirectional"))
      (node (ref "L2") (pin "8") (pinfunction "8_8") (pintype "bidirectional"))
      (node (ref "PICKACHU-5V") (pin "2") (pinfunction "VIN_2") (pintype "bidirectional"))
    )
    (net (code "56") (name "Net-(Q1-G)") (class "Default")
      (node (ref "Q1") (pin "1") (pinfunction "G_1") (pintype "passive"))
      (node (ref "U$11") (pin "7") (pinfunction "GATE_7") (pintype "bidirectional"))
    )
    (net (code "57") (name "Net-(Q1-S)") (class "Default")
      (node (ref "Q1") (pin "3") (pinfunction "S_3") (pintype "passive"))
      (node (ref "U$11") (pin "5") (pinfunction "SENSE+_5") (pintype "bidirectional"))
      (node (ref "U$49") (pin "P$2") (pinfunction "2_P$2") (pintype "passive"))
    )
    (net (code "58") (name "Net-(Q2-G)") (class "Default")
      (node (ref "Q2") (pin "1") (pinfunction "G_1") (pintype "bidirectional"))
      (node (ref "U$17") (pin "7") (pinfunction "GATE_7") (pintype "bidirectional"))
    )
    (net (code "59") (name "Net-(Q2-S)") (class "Default")
      (node (ref "Q2") (pin "3") (pinfunction "S_3") (pintype "bidirectional"))
      (node (ref "R7") (pin "1") (pinfunction "1_1") (pintype "passive"))
    )
    (net (code "60") (name "Net-(Q3-G)") (class "Default")
      (node (ref "Q3") (pin "1") (pinfunction "G_1") (pintype "passive"))
      (node (ref "U$23") (pin "7") (pinfunction "GATE_7") (pintype "bidirectional"))
    )
    (net (code "61") (name "Net-(Q3-S)") (class "Default")
      (node (ref "Q3") (pin "3") (pinfunction "S_3") (pintype "passive"))
      (node (ref "U$23") (pin "5") (pinfunction "SENSE+_5") (pintype "bidirectional"))
      (node (ref "U$50") (pin "P$2") (pinfunction "2_P$2") (pintype "passive"))
    )
    (net (code "62") (name "Net-(Q4-G)") (class "Default")
      (node (ref "Q4") (pin "1") (pinfunction "G_1") (pintype "passive"))
      (node (ref "U$27") (pin "7") (pinfunction "GATE_7") (pintype "bidirectional"))
    )
    (net (code "63") (name "Net-(Q4-S)") (class "Default")
      (node (ref "Q4") (pin "3") (pinfunction "S_3") (pintype "passive"))
      (node (ref "U$27") (pin "5") (pinfunction "SENSE+_5") (pintype "bidirectional"))
      (node (ref "U$48") (pin "P$2") (pinfunction "2_P$2") (pintype "passive"))
    )
    (net (code "64") (name "Net-(Q5-G)") (class "Default")
      (node (ref "Q5") (pin "1") (pinfunction "G_1") (pintype "passive"))
      (node (ref "U$32") (pin "7") (pinfunction "GATE_7") (pintype "bidirectional"))
    )
    (net (code "65") (name "Net-(Q5-S)") (class "Default")
      (node (ref "Q5") (pin "3") (pinfunction "S_3") (pintype "passive"))
      (node (ref "U$32") (pin "5") (pinfunction "SENSE+_5") (pintype "bidirectional"))
      (node (ref "U$47") (pin "P$2") (pinfunction "2_P$2") (pintype "passive"))
    )
    (net (code "66") (name "Net-(Q6-G)") (class "Default")
      (node (ref "Q6") (pin "1") (pinfunction "G_1") (pintype "passive"))
      (node (ref "U$37") (pin "7") (pinfunction "GATE_7") (pintype "bidirectional"))
    )
    (net (code "67") (name "Net-(Q6-S)") (class "Default")
      (node (ref "Q6") (pin "3") (pinfunction "S_3") (pintype "passive"))
      (node (ref "U$37") (pin "5") (pinfunction "SENSE+_5") (pintype "bidirectional"))
      (node (ref "U$45") (pin "P$2") (pinfunction "2_P$2") (pintype "passive"))
    )
    (net (code "68") (name "Net-(Q7-G)") (class "Default")
      (node (ref "Q7") (pin "1") (pinfunction "G_1") (pintype "passive"))
      (node (ref "U$41") (pin "7") (pinfunction "GATE_7") (pintype "bidirectional"))
    )
    (net (code "69") (name "Net-(Q7-S)") (class "Default")
      (node (ref "Q7") (pin "3") (pinfunction "S_3") (pintype "passive"))
      (node (ref "U$41") (pin "5") (pinfunction "SENSE+_5") (pintype "bidirectional"))
      (node (ref "U$46") (pin "P$2") (pinfunction "2_P$2") (pintype "passive"))
    )
    (net (code "70") (name "Net-(Q9-A)") (class "Default")
      (node (ref "Q9") (pin "8") (pinfunction "A_8") (pintype "bidirectional"))
      (node (ref "R8") (pin "1") (pinfunction "1_1") (pintype "passive"))
      (node (ref "U$64") (pin "3") (pinfunction "3+RECEIVE+_3") (pintype "bidirectional"))
    )
    (net (code "71") (name "Net-(Q9-B)") (class "Default")
      (node (ref "Q9") (pin "7") (pinfunction "B_7") (pintype "bidirectional"))
      (node (ref "R8") (pin "2") (pinfunction "2_2") (pintype "passive"))
      (node (ref "U$64") (pin "6") (pinfunction "6-RECEIVE-_6") (pintype "bidirectional"))
    )
    (net (code "72") (name "Net-(Q9-D)") (class "Default")
      (node (ref "Q9") (pin "3") (pinfunction "D_3") (pintype "bidirectional"))
      (node (ref "U$57") (pin "3") (pinfunction "PD1_3") (pintype "bidirectional"))
    )
    (net (code "73") (name "Net-(Q9-R)") (class "Default")
      (node (ref "Q9") (pin "2") (pinfunction "R_2") (pintype "bidirectional"))
      (node (ref "U$57") (pin "2") (pinfunction "PD0_2") (pintype "bidirectional"))
    )
    (net (code "74") (name "Net-(Q9-Y)") (class "Default")
      (node (ref "Q9") (pin "5") (pinfunction "Y_5") (pintype "bidirectional"))
      (node (ref "R6") (pin "2") (pinfunction "2_2") (pintype "passive"))
      (node (ref "U$64") (pin "1") (pinfunction "1-TRANS+_1") (pintype "bidirectional"))
    )
    (net (code "75") (name "Net-(Q9-Z)") (class "Default")
      (node (ref "Q9") (pin "6") (pinfunction "Z_6") (pintype "bidirectional"))
      (node (ref "R6") (pin "1") (pinfunction "1_1") (pintype "passive"))
      (node (ref "U$64") (pin "2") (pinfunction "2-TRANS-_2") (pintype "bidirectional"))
    )
    (net (code "76") (name "Net-(Q10-G)") (class "Default")
      (node (ref "Q10") (pin "2") (pinfunction "G_2") (pintype "bidirectional"))
      (node (ref "R19") (pin "2") (pinfunction "2_2") (pintype "passive"))
    )
    (net (code "77") (name "Net-(Q11-D)") (class "Default")
      (node (ref "Q11") (pin "3") (pinfunction "D_3") (pintype "bidirectional"))
      (node (ref "ZAPDOS-20V") (pin "3") (pinfunction "INHIBIT_3") (pintype "bidirectional"))
    )
    (net (code "78") (name "Net-(Q11-G)") (class "Default")
      (node (ref "Q11") (pin "2") (pinfunction "G_2") (pintype "bidirectional"))
      (node (ref "R13") (pin "2") (pinfunction "2_2") (pintype "passive"))
    )
    (net (code "79") (name "Net-(Q12-G)") (class "Default")
      (node (ref "Q12") (pin "2") (pinfunction "G_2") (pintype "bidirectional"))
      (node (ref "R14") (pin "2") (pinfunction "2_2") (pintype "passive"))
    )
    (net (code "80") (name "Net-(Q14-G)") (class "Default")
      (node (ref "Q14") (pin "2") (pinfunction "G_2") (pintype "bidirectional"))
      (node (ref "R17") (pin "2") (pinfunction "2_2") (pintype "passive"))
    )
    (net (code "81") (name "Net-(Q15-G)") (class "Default")
      (node (ref "Q15") (pin "1") (pinfunction "G_1") (pintype "passive"))
      (node (ref "U$70") (pin "7") (pinfunction "GATE_7") (pintype "bidirectional"))
    )
    (net (code "82") (name "Net-(Q15-S)") (class "Default")
      (node (ref "Q15") (pin "3") (pinfunction "S_3") (pintype "passive"))
      (node (ref "U$70") (pin "5") (pinfunction "SENSE+_5") (pintype "bidirectional"))
      (node (ref "U$73") (pin "P$2") (pinfunction "2_P$2") (pintype "passive"))
    )
    (net (code "83") (name "Net-(R25-Pad2)") (class "Default")
      (node (ref "R25") (pin "2") (pinfunction "2_2") (pintype "passive"))
      (node (ref "R9") (pin "2") (pinfunction "2_2") (pintype "passive"))
    )
    (net (code "84") (name "Net-(RAICHU-5V-CRIT-ADJUST)") (class "Default")
      (node (ref "R3") (pin "2") (pinfunction "2_2") (pintype "passive"))
      (node (ref "RAICHU-5V-CRIT") (pin "4") (pinfunction "ADJUST_4") (pintype "bidirectional"))
    )
    (net (code "85") (name "Net-(RAICHU-5V-CRIT-SENSE)") (class "Default")
      (node (ref "C15") (pin "+") (pinfunction "+_+") (pintype "passive"))
      (node (ref "L4") (pin "1") (pinfunction "1_1") (pintype "bidirectional"))
      (node (ref "L4") (pin "2") (pinfunction "2_2") (pintype "bidirectional"))
      (node (ref "L4") (pin "3") (pinfunction "3_3") (pintype "bidirectional"))
      (node (ref "L4") (pin "4") (pinfunction "4_4") (pintype "bidirectional"))
      (node (ref "RAICHU-5V-CRIT") (pin "5") (pinfunction "SENSE_5") (pintype "bidirectional"))
      (node (ref "RAICHU-5V-CRIT") (pin "6") (pinfunction "VOUT_6") (pintype "bidirectional"))
    )
    (net (code "86") (name "Net-(RAICHU-5V-CRIT-VIN)") (class "Default")
      (node (ref "C4") (pin "2") (pinfunction "2_2") (pintype "passive"))
      (node (ref "L1") (pin "5") (pinfunction "5_5") (pintype "bidirectional"))
      (node (ref "L1") (pin "6") (pinfunction "6_6") (pintype "bidirectional"))
      (node (ref "L1") (pin "7") (pinfunction "7_7") (pintype "bidirectional"))
      (node (ref "L1") (pin "8") (pinfunction "8_8") (pintype "bidirectional"))
      (node (ref "RAICHU-5V-CRIT") (pin "2") (pinfunction "VIN_2") (pintype "bidirectional"))
    )
    (net (code "87") (name "Net-(U$11-CT)") (class "Default")
      (node (ref "C41") (pin "1") (pinfunction "1_1") (pintype "passive"))
      (node (ref "U$11") (pin "3") (pinfunction "CT_3") (pintype "bidirectional"))
    )
    (net (code "88") (name "Net-(U$11-INPUT)") (class "Default")
      (node (ref "R18") (pin "2") (pinfunction "2_2") (pintype "passive"))
      (node (ref "U$11") (pin "2") (pinfunction "INPUT_2") (pintype "bidirectional"))
    )
    (net (code "89") (name "Net-(U$11-SENSE-)") (class "Default")
      (node (ref "U$11") (pin "6") (pinfunction "SENSE-_6") (pintype "bidirectional"))
      (node (ref "U$14") (pin "P$1") (pinfunction "P$1_P$1") (pintype "bidirectional"))
      (node (ref "U$49") (pin "P$1") (pinfunction "1_P$1") (pintype "passive"))
    )
    (net (code "90") (name "Net-(U$11-VBOOST)") (class "Default")
      (node (ref "C35") (pin "2") (pinfunction "2_2") (pintype "passive"))
      (node (ref "U$11") (pin "8") (pinfunction "VBOOST_8") (pintype "bidirectional"))
    )
    (net (code "91") (name "Net-(U$13-OUT)") (class "Default")
      (node (ref "U$13") (pin "2") (pinfunction "OUT_2") (pintype "bidirectional"))
      (node (ref "U$57") (pin "23") (pinfunction "PC0_23") (pintype "bidirectional"))
    )
    (net (code "92") (name "Net-(U$16-S+)") (class "Default")
      (node (ref "C55") (pin "1") (pinfunction "1_1") (pintype "passive"))
      (node (ref "R7") (pin "SENSE1") (pinfunction "SENSE1_SENSE1") (pintype "bidirectional"))
      (node (ref "U$16") (pin "2") (pinfunction "S+_2") (pintype "bidirectional"))
      (node (ref "U$17") (pin "5") (pinfunction "SENSE+_5") (pintype "bidirectional"))
    )
    (net (code "93") (name "Net-(U$16-S-)") (class "Default")
      (node (ref "C55") (pin "2") (pinfunction "2_2") (pintype "passive"))
      (node (ref "R32") (pin "1") (pinfunction "1_1") (pintype "passive"))
      (node (ref "U$16") (pin "1") (pinfunction "S-_1") (pintype "bidirectional"))
    )
    (net (code "94") (name "Net-(U$17-CT)") (class "Default")
      (node (ref "C21") (pin "2") (pinfunction "2_2") (pintype "passive"))
      (node (ref "U$17") (pin "3") (pinfunction "CT_3") (pintype "bidirectional"))
    )
    (net (code "95") (name "Net-(U$17-INPUT)") (class "Default")
      (node (ref "R16") (pin "2") (pinfunction "2_2") (pintype "passive"))
      (node (ref "U$17") (pin "2") (pinfunction "INPUT_2") (pintype "bidirectional"))
    )
    (net (code "96") (name "Net-(U$17-SENSE-)") (class "Default")
      (node (ref "R32") (pin "2") (pinfunction "2_2") (pintype "passive"))
      (node (ref "R7") (pin "SENSE2") (pinfunction "SENSE2_SENSE2") (pintype "bidirectional"))
      (node (ref "U$17") (pin "6") (pinfunction "SENSE-_6") (pintype "bidirectional"))
    )
    (net (code "97") (name "Net-(U$17-VBOOST)") (class "Default")
      (node (ref "C20") (pin "2") (pinfunction "2_2") (pintype "passive"))
      (node (ref "U$17") (pin "8") (pinfunction "VBOOST_8") (pintype "bidirectional"))
    )
    (net (code "98") (name "Net-(U$23-CT)") (class "Default")
      (node (ref "C37") (pin "1") (pinfunction "1_1") (pintype "passive"))
      (node (ref "U$23") (pin "3") (pinfunction "CT_3") (pintype "bidirectional"))
    )
    (net (code "99") (name "Net-(U$23-INPUT)") (class "Default")
      (node (ref "R23") (pin "2") (pinfunction "2_2") (pintype "passive"))
      (node (ref "U$23") (pin "2") (pinfunction "INPUT_2") (pintype "bidirectional"))
    )
    (net (code "100") (name "Net-(U$23-SENSE-)") (class "Default")
      (node (ref "U$23") (pin "6") (pinfunction "SENSE-_6") (pintype "bidirectional"))
      (node (ref "U$26") (pin "P$1") (pinfunction "P$1_P$1") (pintype "bidirectional"))
      (node (ref "U$50") (pin "P$1") (pinfunction "1_P$1") (pintype "passive"))
    )
    (net (code "101") (name "Net-(U$23-VBOOST)") (class "Default")
      (node (ref "C31") (pin "2") (pinfunction "2_2") (pintype "passive"))
      (node (ref "U$23") (pin "8") (pinfunction "VBOOST_8") (pintype "bidirectional"))
    )
    (net (code "102") (name "Net-(U$27-CT)") (class "Default")
      (node (ref "C40") (pin "1") (pinfunction "1_1") (pintype "passive"))
      (node (ref "U$27") (pin "3") (pinfunction "CT_3") (pintype "bidirectional"))
    )
    (net (code "103") (name "Net-(U$27-INPUT)") (class "Default")
      (node (ref "R15") (pin "2") (pinfunction "2_2") (pintype "passive"))
      (node (ref "U$27") (pin "2") (pinfunction "INPUT_2") (pintype "bidirectional"))
    )
    (net (code "104") (name "Net-(U$27-SENSE-)") (class "Default")
      (node (ref "U$27") (pin "6") (pinfunction "SENSE-_6") (pintype "bidirectional"))
      (node (ref "U$31") (pin "P$1") (pinfunction "P$1_P$1") (pintype "bidirectional"))
      (node (ref "U$48") (pin "P$1") (pinfunction "1_P$1") (pintype "passive"))
    )
    (net (code "105") (name "Net-(U$27-VBOOST)") (class "Default")
      (node (ref "C34") (pin "2") (pinfunction "2_2") (pintype "passive"))
      (node (ref "U$27") (pin "8") (pinfunction "VBOOST_8") (pintype "bidirectional"))
    )
    (net (code "106") (name "Net-(U$32-CT)") (class "Default")
      (node (ref "C36") (pin "1") (pinfunction "1_1") (pintype "passive"))
      (node (ref "U$32") (pin "3") (pinfunction "CT_3") (pintype "bidirectional"))
    )
    (net (code "107") (name "Net-(U$32-INPUT)") (class "Default")
      (node (ref "R22") (pin "2") (pinfunction "2_2") (pintype "passive"))
      (node (ref "U$32") (pin "2") (pinfunction "INPUT_2") (pintype "bidirectional"))
    )
    (net (code "108") (name "Net-(U$32-SENSE-)") (class "Default")
      (node (ref "U$32") (pin "6") (pinfunction "SENSE-_6") (pintype "bidirectional"))
      (node (ref "U$36") (pin "P$1") (pinfunction "P$1_P$1") (pintype "bidirectional"))
      (node (ref "U$47") (pin "P$1") (pinfunction "1_P$1") (pintype "passive"))
    )
    (net (code "109") (name "Net-(U$32-VBOOST)") (class "Default")
      (node (ref "C30") (pin "2") (pinfunction "2_2") (pintype "passive"))
      (node (ref "U$32") (pin "8") (pinfunction "VBOOST_8") (pintype "bidirectional"))
    )
    (net (code "110") (name "Net-(U$37-CT)") (class "Default")
      (node (ref "C39") (pin "1") (pinfunction "1_1") (pintype "passive"))
      (node (ref "U$37") (pin "3") (pinfunction "CT_3") (pintype "bidirectional"))
    )
    (net (code "111") (name "Net-(U$37-INPUT)") (class "Default")
      (node (ref "R20") (pin "2") (pinfunction "2_2") (pintype "passive"))
      (node (ref "U$37") (pin "2") (pinfunction "INPUT_2") (pintype "bidirectional"))
    )
    (net (code "112") (name "Net-(U$37-SENSE-)") (class "Default")
      (node (ref "U$37") (pin "6") (pinfunction "SENSE-_6") (pintype "bidirectional"))
      (node (ref "U$40") (pin "P$1") (pinfunction "P$1_P$1") (pintype "bidirectional"))
      (node (ref "U$45") (pin "P$1") (pinfunction "1_P$1") (pintype "passive"))
    )
    (net (code "113") (name "Net-(U$37-VBOOST)") (class "Default")
      (node (ref "C33") (pin "2") (pinfunction "2_2") (pintype "passive"))
      (node (ref "U$37") (pin "8") (pinfunction "VBOOST_8") (pintype "bidirectional"))
    )
    (net (code "114") (name "Net-(U$41-CT)") (class "Default")
      (node (ref "C38") (pin "1") (pinfunction "1_1") (pintype "passive"))
      (node (ref "U$41") (pin "3") (pinfunction "CT_3") (pintype "bidirectional"))
    )
    (net (code "115") (name "Net-(U$41-INPUT)") (class "Default")
      (node (ref "R21") (pin "2") (pinfunction "2_2") (pintype "passive"))
      (node (ref "U$41") (pin "2") (pinfunction "INPUT_2") (pintype "bidirectional"))
    )
    (net (code "116") (name "Net-(U$41-SENSE-)") (class "Default")
      (node (ref "U$41") (pin "6") (pinfunction "SENSE-_6") (pintype "bidirectional"))
      (node (ref "U$44") (pin "P$1") (pinfunction "P$1_P$1") (pintype "bidirectional"))
      (node (ref "U$46") (pin "P$1") (pinfunction "1_P$1") (pintype "passive"))
    )
    (net (code "117") (name "Net-(U$41-VBOOST)") (class "Default")
      (node (ref "C32") (pin "2") (pinfunction "2_2") (pintype "passive"))
      (node (ref "U$41") (pin "8") (pinfunction "VBOOST_8") (pintype "bidirectional"))
    )
    (net (code "118") (name "Net-(U$57-XTAL1)") (class "Default")
      (node (ref "C5") (pin "2") (pinfunction "2_2") (pintype "passive"))
      (node (ref "U$57") (pin "9") (pinfunction "XTAL1_9") (pintype "bidirectional"))
      (node (ref "X1") (pin "P$2") (pinfunction "2_P$2") (pintype "passive"))
    )
    (net (code "119") (name "Net-(U$57-XTAL2)") (class "Default")
      (node (ref "C6") (pin "2") (pinfunction "2_2") (pintype "passive"))
      (node (ref "U$57") (pin "10") (pinfunction "XTAL2_10") (pintype "bidirectional"))
      (node (ref "X1") (pin "P$1") (pinfunction "1_P$1") (pintype "passive"))
    )
    (net (code "120") (name "Net-(U$70-CT)") (class "Default")
      (node (ref "C49") (pin "1") (pinfunction "1_1") (pintype "passive"))
      (node (ref "U$70") (pin "3") (pinfunction "CT_3") (pintype "bidirectional"))
    )
    (net (code "121") (name "Net-(U$70-INPUT)") (class "Default")
      (node (ref "R24") (pin "2") (pinfunction "2_2") (pintype "passive"))
      (node (ref "U$70") (pin "2") (pinfunction "INPUT_2") (pintype "bidirectional"))
    )
    (net (code "122") (name "Net-(U$70-SENSE-)") (class "Default")
      (node (ref "U$70") (pin "6") (pinfunction "SENSE-_6") (pintype "bidirectional"))
      (node (ref "U$72") (pin "P$1") (pinfunction "P$1_P$1") (pintype "bidirectional"))
      (node (ref "U$73") (pin "P$1") (pinfunction "1_P$1") (pintype "passive"))
    )
    (net (code "123") (name "Net-(U$70-VBOOST)") (class "Default")
      (node (ref "C48") (pin "2") (pinfunction "2_2") (pintype "passive"))
      (node (ref "U$70") (pin "8") (pinfunction "VBOOST_8") (pintype "bidirectional"))
    )
    (net (code "124") (name "Net-(ZAPDOS-20V-ADJUST)") (class "Default")
      (node (ref "R12") (pin "2") (pinfunction "2_2") (pintype "passive"))
      (node (ref "ZAPDOS-20V") (pin "4") (pinfunction "ADJUST_4") (pintype "bidirectional"))
    )
    (net (code "125") (name "Net-(ZAPDOS-20V-SENSE)") (class "Default")
      (node (ref "C17") (pin "+") (pinfunction "+_+") (pintype "passive"))
      (node (ref "L10") (pin "1") (pinfunction "1_1") (pintype "bidirectional"))
      (node (ref "L10") (pin "2") (pinfunction "2_2") (pintype "bidirectional"))
      (node (ref "L10") (pin "3") (pinfunction "3_3") (pintype "bidirectional"))
      (node (ref "L10") (pin "4") (pinfunction "4_4") (pintype "bidirectional"))
      (node (ref "ZAPDOS-20V") (pin "5") (pinfunction "SENSE_5") (pintype "bidirectional"))
      (node (ref "ZAPDOS-20V") (pin "6") (pinfunction "VOUT_6") (pintype "bidirectional"))
    )
    (net (code "126") (name "Net-(ZAPDOS-20V-VIN)") (class "Default")
      (node (ref "C29") (pin "2") (pinfunction "2_2") (pintype "passive"))
      (node (ref "L9") (pin "5") (pinfunction "5_5") (pintype "bidirectional"))
      (node (ref "L9") (pin "6") (pinfunction "6_6") (pintype "bidirectional"))
      (node (ref "L9") (pin "7") (pinfunction "7_7") (pintype "bidirectional"))
      (node (ref "L9") (pin "8") (pinfunction "8_8") (pintype "bidirectional"))
      (node (ref "ZAPDOS-20V") (pin "2") (pinfunction "VIN_2") (pintype "bidirectional"))
    )
    (net (code "127") (name "S_12V-2") (class "Default")
      (node (ref "R14") (pin "1") (pinfunction "1_1") (pintype "passive"))
      (node (ref "U$57") (pin "6") (pinfunction "PD4_6") (pintype "bidirectional"))
    )
    (net (code "128") (name "S_MAIN") (class "Default")
      (node (ref "R16") (pin "1") (pinfunction "1_1") (pintype "passive"))
      (node (ref "U$57") (pin "4") (pinfunction "PD2_4") (pintype "bidirectional"))
    )
    (net (code "129") (name "S_MC1") (class "Default")
      (node (ref "R22") (pin "1") (pinfunction "1_1") (pintype "passive"))
      (node (ref "U$57") (pin "14") (pinfunction "PB0_14") (pintype "bidirectional"))
    )
    (net (code "130") (name "S_MC2") (class "Default")
      (node (ref "R21") (pin "1") (pinfunction "1_1") (pintype "passive"))
      (node (ref "U$57") (pin "13") (pinfunction "PD7_13") (pintype "bidirectional"))
    )
    (net (code "131") (name "S_MC3") (class "Default")
      (node (ref "R20") (pin "1") (pinfunction "1_1") (pintype "passive"))
      (node (ref "U$57") (pin "12") (pinfunction "PD6_12") (pintype "bidirectional"))
    )
    (net (code "132") (name "S_MC4") (class "Default")
      (node (ref "R18") (pin "1") (pinfunction "1_1") (pintype "passive"))
      (node (ref "U$57") (pin "11") (pinfunction "PD5_11") (pintype "bidirectional"))
    )
    (net (code "133") (name "S_MC5") (class "Default")
      (node (ref "R15") (pin "1") (pinfunction "1_1") (pintype "passive"))
      (node (ref "U$57") (pin "16") (pinfunction "PB2_16") (pintype "bidirectional"))
    )
    (net (code "134") (name "S_MC6") (class "Default")
      (node (ref "R23") (pin "1") (pinfunction "1_1") (pintype "passive"))
      (node (ref "U$57") (pin "17") (pinfunction "PB3_17") (pintype "bidirectional"))
    )
    (net (code "135") (name "S_POE") (class "Default")
      (node (ref "R13") (pin "1") (pinfunction "1_1") (pintype "passive"))
      (node (ref "U$57") (pin "5") (pinfunction "PD3_5") (pintype "bidirectional"))
    )
    (net (code "136") (name "S_V5-2") (class "Default")
      (node (ref "R17") (pin "1") (pinfunction "1_1") (pintype "passive"))
      (node (ref "U$57") (pin "18") (pinfunction "PB4_18") (pintype "bidirectional"))
    )
    (net (code "137") (name "S_V12-1") (class "Default")
      (node (ref "R19") (pin "1") (pinfunction "1_1") (pintype "passive"))
      (node (ref "U$57") (pin "19") (pinfunction "PB5_19") (pintype "bidirectional"))
    )
    (net (code "138") (name "S_V24AUX") (class "Default")
      (node (ref "R24") (pin "1") (pinfunction "1_1") (pintype "passive"))
      (node (ref "U$57") (pin "15") (pinfunction "PB1_15") (pintype "bidirectional"))
    )
    (net (code "139") (name "V1") (class "Default")
      (node (ref "C16") (pin "1") (pinfunction "1_1") (pintype "passive"))
      (node (ref "C20") (pin "1") (pinfunction "1_1") (pintype "passive"))
      (node (ref "D5") (pin "C") (pinfunction "K_C") (pintype "passive"))
      (node (ref "J2") (pin "PIN1-1") (pinfunction "1-1_PIN1-1") (pintype "bidirectional"))
      (node (ref "J2") (pin "PIN1-2") (pinfunction "1-2_PIN1-2") (pintype "bidirectional"))
      (node (ref "Q2") (pin "2") (pinfunction "D_2") (pintype "bidirectional"))
      (node (ref "Q8") (pin "1") (pinfunction "VIN_1") (pintype "bidirectional"))
      (node (ref "R25") (pin "1") (pinfunction "1_1") (pintype "passive"))
      (node (ref "U$17") (pin "1") (pinfunction "VDD_1") (pintype "bidirectional"))
    )
    (net (code "140") (name "V24") (class "Default")
      (node (ref "C10") (pin "2") (pinfunction "2_2") (pintype "passive"))
      (node (ref "C19") (pin "2") (pinfunction "2_2") (pintype "passive"))
      (node (ref "C24") (pin "2") (pinfunction "2_2") (pintype "passive"))
      (node (ref "C28") (pin "2") (pinfunction "2_2") (pintype "passive"))
      (node (ref "C30") (pin "1") (pinfunction "1_1") (pintype "passive"))
      (node (ref "C31") (pin "1") (pinfunction "1_1") (pintype "passive"))
      (node (ref "C32") (pin "1") (pinfunction "1_1") (pintype "passive"))
      (node (ref "C33") (pin "1") (pinfunction "1_1") (pintype "passive"))
      (node (ref "C34") (pin "1") (pinfunction "1_1") (pintype "passive"))
      (node (ref "C35") (pin "1") (pinfunction "1_1") (pintype "passive"))
      (node (ref "C42") (pin "1") (pinfunction "1_1") (pintype "passive"))
      (node (ref "C43") (pin "1") (pinfunction "1_1") (pintype "passive"))
      (node (ref "C44") (pin "1") (pinfunction "1_1") (pintype "passive"))
      (node (ref "C45") (pin "1") (pinfunction "1_1") (pintype "passive"))
      (node (ref "C46") (pin "1") (pinfunction "1_1") (pintype "passive"))
      (node (ref "C47") (pin "1") (pinfunction "1_1") (pintype "passive"))
      (node (ref "C48") (pin "1") (pinfunction "1_1") (pintype "passive"))
      (node (ref "C50") (pin "1") (pinfunction "1_1") (pintype "passive"))
      (node (ref "C58") (pin "P$1") (pinfunction "+_P$1") (pintype "passive"))
      (node (ref "C59") (pin "P$1") (pinfunction "+_P$1") (pintype "passive"))
      (node (ref "C60") (pin "P$1") (pinfunction "+_P$1") (pintype "passive"))
      (node (ref "C61") (pin "P$1") (pinfunction "+_P$1") (pintype "passive"))
      (node (ref "C62") (pin "P$1") (pinfunction "+_P$1") (pintype "passive"))
      (node (ref "C63") (pin "P$1") (pinfunction "+_P$1") (pintype "passive"))
      (node (ref "C64") (pin "P$1") (pinfunction "+_P$1") (pintype "passive"))
      (node (ref "C65") (pin "P$1") (pinfunction "+_P$1") (pintype "passive"))
      (node (ref "C66") (pin "P$1") (pinfunction "+_P$1") (pintype "passive"))
      (node (ref "C67") (pin "P$1") (pinfunction "+_P$1") (pintype "passive"))
      (node (ref "C9") (pin "2") (pinfunction "2_2") (pintype "passive"))
      (node (ref "D10") (pin "C") (pinfunction "K_C") (pintype "passive"))
      (node (ref "D4") (pin "C") (pinfunction "K_C") (pintype "passive"))
      (node (ref "L1") (pin "1") (pinfunction "1_1") (pintype "bidirectional"))
      (node (ref "L1") (pin "2") (pinfunction "2_2") (pintype "bidirectional"))
      (node (ref "L1") (pin "3") (pinfunction "3_3") (pintype "bidirectional"))
      (node (ref "L1") (pin "4") (pinfunction "4_4") (pintype "bidirectional"))
      (node (ref "L2") (pin "1") (pinfunction "1_1") (pintype "bidirectional"))
      (node (ref "L2") (pin "2") (pinfunction "2_2") (pintype "bidirectional"))
      (node (ref "L2") (pin "3") (pinfunction "3_3") (pintype "bidirectional"))
      (node (ref "L2") (pin "4") (pinfunction "4_4") (pintype "bidirectional"))
      (node (ref "L5") (pin "1") (pinfunction "1_1") (pintype "bidirectional"))
      (node (ref "L5") (pin "2") (pinfunction "2_2") (pintype "bidirectional"))
      (node (ref "L5") (pin "3") (pinfunction "3_3") (pintype "bidirectional"))
      (node (ref "L5") (pin "4") (pinfunction "4_4") (pintype "bidirectional"))
      (node (ref "L7") (pin "1") (pinfunction "1_1") (pintype "bidirectional"))
      (node (ref "L7") (pin "2") (pinfunction "2_2") (pintype "bidirectional"))
      (node (ref "L7") (pin "3") (pinfunction "3_3") (pintype "bidirectional"))
      (node (ref "L7") (pin "4") (pinfunction "4_4") (pintype "bidirectional"))
      (node (ref "L9") (pin "1") (pinfunction "1_1") (pintype "bidirectional"))
      (node (ref "L9") (pin "2") (pinfunction "2_2") (pintype "bidirectional"))
      (node (ref "L9") (pin "3") (pinfunction "3_3") (pintype "bidirectional"))
      (node (ref "L9") (pin "4") (pinfunction "4_4") (pintype "bidirectional"))
      (node (ref "Q1") (pin "2") (pinfunction "D_2") (pintype "passive"))
      (node (ref "Q15") (pin "2") (pinfunction "D_2") (pintype "passive"))
      (node (ref "Q3") (pin "2") (pinfunction "D_2") (pintype "passive"))
      (node (ref "Q4") (pin "2") (pinfunction "D_2") (pintype "passive"))
      (node (ref "Q5") (pin "2") (pinfunction "D_2") (pintype "passive"))
      (node (ref "Q6") (pin "2") (pinfunction "D_2") (pintype "passive"))
      (node (ref "Q7") (pin "2") (pinfunction "D_2") (pintype "passive"))
      (node (ref "R7") (pin "2") (pinfunction "2_2") (pintype "passive"))
      (node (ref "U$11") (pin "1") (pinfunction "VDD_1") (pintype "bidirectional"))
      (node (ref "U$23") (pin "1") (pinfunction "VDD_1") (pintype "bidirectional"))
      (node (ref "U$27") (pin "1") (pinfunction "VDD_1") (pintype "bidirectional"))
      (node (ref "U$32") (pin "1") (pinfunction "VDD_1") (pintype "bidirectional"))
      (node (ref "U$37") (pin "1") (pinfunction "VDD_1") (pintype "bidirectional"))
      (node (ref "U$41") (pin "1") (pinfunction "VDD_1") (pintype "bidirectional"))
      (node (ref "U$70") (pin "1") (pinfunction "VDD_1") (pintype "bidirectional"))
    )
    (net (code "141") (name "VA5") (class "Default")
      (node (ref "C11") (pin "1") (pinfunction "1_1") (pintype "passive"))
      (node (ref "C12") (pin "2") (pinfunction "2_2") (pintype "passive"))
      (node (ref "C13") (pin "1") (pinfunction "1_1") (pintype "passive"))
      (node (ref "C51") (pin "2") (pinfunction "2_2") (pintype "passive"))
      (node (ref "Q8") (pin "3") (pinfunction "VOUT_3") (pintype "bidirectional"))
      (node (ref "Q9") (pin "1") (pinfunction "VCC_1") (pintype "bidirectional"))
      (node (ref "R1") (pin "2") (pinfunction "2_2") (pintype "passive"))
      (node (ref "U$13") (pin "3") (pinfunction "VIN_3") (pintype "bidirectional"))
      (node (ref "U$57") (pin "20") (pinfunction "AVCC_20") (pintype "bidirectional"))
      (node (ref "U$57") (pin "7") (pinfunction "VCC_7") (pintype "bidirectional"))
    )
    (net (code "142") (name "V_ANTENNA") (class "Default")
      (node (ref "C56") (pin "+") (pinfunction "+_+") (pintype "passive"))
      (node (ref "C57") (pin "1") (pinfunction "1_1") (pintype "passive"))
      (node (ref "D8") (pin "C") (pinfunction "K_C") (pintype "passive"))
      (node (ref "D9") (pin "C") (pinfunction "K_C") (pintype "passive"))
      (node (ref "N1") (pin "1-4") (pinfunction "4-DC+_1-4") (pintype "bidirectional"))
      (node (ref "N1") (pin "1-5") (pinfunction "5-DC++_1-5") (pintype "bidirectional"))
    )
    (net (code "143") (name "V_POE") (class "Default")
      (node (ref "C27") (pin "1") (pinfunction "1_1") (pintype "passive"))
      (node (ref "C68") (pin "1") (pinfunction "1_1") (pintype "passive"))
      (node (ref "C69") (pin "1") (pinfunction "1_1") (pintype "passive"))
      (node (ref "C70") (pin "1") (pinfunction "1_1") (pintype "passive"))
      (node (ref "D6") (pin "C") (pinfunction "K_C") (pintype "passive"))
      (node (ref "D8") (pin "A") (pinfunction "A_A") (pintype "passive"))
      (node (ref "L10") (pin "5") (pinfunction "5_5") (pintype "bidirectional"))
      (node (ref "L10") (pin "6") (pinfunction "6_6") (pintype "bidirectional"))
      (node (ref "L10") (pin "7") (pinfunction "7_7") (pintype "bidirectional"))
      (node (ref "L10") (pin "8") (pinfunction "8_8") (pintype "bidirectional"))
      (node (ref "N2") (pin "1-4") (pinfunction "4-DC+_1-4") (pintype "bidirectional"))
      (node (ref "N2") (pin "1-5") (pinfunction "5-DC++_1-5") (pintype "bidirectional"))
      (node (ref "N3") (pin "1-4") (pinfunction "4-DC+_1-4") (pintype "bidirectional"))
      (node (ref "N3") (pin "1-5") (pinfunction "5-DC++_1-5") (pintype "bidirectional"))
      (node (ref "N4") (pin "1-4") (pinfunction "4-DC+_1-4") (pintype "bidirectional"))
      (node (ref "N4") (pin "1-5") (pinfunction "5-DC++_1-5") (pintype "bidirectional"))
      (node (ref "N5") (pin "1-4") (pinfunction "4-DC+_1-4") (pintype "bidirectional"))
      (node (ref "N5") (pin "1-5") (pinfunction "5-DC++_1-5") (pintype "bidirectional"))
      (node (ref "N6") (pin "1-4") (pinfunction "4-DC+_1-4") (pintype "bidirectional"))
      (node (ref "N6") (pin "1-5") (pinfunction "5-DC++_1-5") (pintype "bidirectional"))
      (node (ref "N7") (pin "1-4") (pinfunction "4-DC+_1-4") (pintype "bidirectional"))
      (node (ref "N7") (pin "1-5") (pinfunction "5-DC++_1-5") (pintype "bidirectional"))
      (node (ref "N8") (pin "1-4") (pinfunction "4-DC+_1-4") (pintype "bidirectional"))
      (node (ref "N8") (pin "1-5") (pinfunction "5-DC++_1-5") (pintype "bidirectional"))
    )
    (net (code "144") (name "unconnected-(D9-PadA)") (class "Default")
      (node (ref "D9") (pin "A") (pinfunction "A_A") (pintype "passive"))
    )
    (net (code "145") (name "unconnected-(H1-Pad1)") (class "Default")
      (node (ref "H1") (pin "1") (pinfunction "1_1") (pintype "passive"))
    )
    (net (code "146") (name "unconnected-(H2-Pad1)") (class "Default")
      (node (ref "H2") (pin "1") (pinfunction "1_1") (pintype "passive"))
    )
    (net (code "147") (name "unconnected-(H3-Pad1)") (class "Default")
      (node (ref "H3") (pin "1") (pinfunction "1_1") (pintype "passive"))
    )
    (net (code "148") (name "unconnected-(H4-Pad1)") (class "Default")
      (node (ref "H4") (pin "1") (pinfunction "1_1") (pintype "passive"))
    )
    (net (code "149") (name "unconnected-(N1B-4-DC+-Pad2-4)") (class "Default")
      (node (ref "N1") (pin "2-4") (pinfunction "4-DC+_2-4") (pintype "bidirectional"))
    )
    (net (code "150") (name "unconnected-(N1B-5-DC++-Pad2-5)") (class "Default")
      (node (ref "N1") (pin "2-5") (pinfunction "5-DC++_2-5") (pintype "bidirectional"))
    )
    (net (code "151") (name "unconnected-(N2B-4-DC+-Pad2-4)") (class "Default")
      (node (ref "N2") (pin "2-4") (pinfunction "4-DC+_2-4") (pintype "bidirectional"))
    )
    (net (code "152") (name "unconnected-(N2B-5-DC++-Pad2-5)") (class "Default")
      (node (ref "N2") (pin "2-5") (pinfunction "5-DC++_2-5") (pintype "bidirectional"))
    )
    (net (code "153") (name "unconnected-(N3B-4-DC+-Pad2-4)") (class "Default")
      (node (ref "N3") (pin "2-4") (pinfunction "4-DC+_2-4") (pintype "bidirectional"))
    )
    (net (code "154") (name "unconnected-(N3B-5-DC++-Pad2-5)") (class "Default")
      (node (ref "N3") (pin "2-5") (pinfunction "5-DC++_2-5") (pintype "bidirectional"))
    )
    (net (code "155") (name "unconnected-(N4B-4-DC+-Pad2-4)") (class "Default")
      (node (ref "N4") (pin "2-4") (pinfunction "4-DC+_2-4") (pintype "bidirectional"))
    )
    (net (code "156") (name "unconnected-(N4B-5-DC++-Pad2-5)") (class "Default")
      (node (ref "N4") (pin "2-5") (pinfunction "5-DC++_2-5") (pintype "bidirectional"))
    )
    (net (code "157") (name "unconnected-(N5B-4-DC+-Pad2-4)") (class "Default")
      (node (ref "N5") (pin "2-4") (pinfunction "4-DC+_2-4") (pintype "bidirectional"))
    )
    (net (code "158") (name "unconnected-(N5B-5-DC++-Pad2-5)") (class "Default")
      (node (ref "N5") (pin "2-5") (pinfunction "5-DC++_2-5") (pintype "bidirectional"))
    )
    (net (code "159") (name "unconnected-(N6B-4-DC+-Pad2-4)") (class "Default")
      (node (ref "N6") (pin "2-4") (pinfunction "4-DC+_2-4") (pintype "bidirectional"))
    )
    (net (code "160") (name "unconnected-(N6B-5-DC++-Pad2-5)") (class "Default")
      (node (ref "N6") (pin "2-5") (pinfunction "5-DC++_2-5") (pintype "bidirectional"))
    )
    (net (code "161") (name "unconnected-(N7B-4-DC+-Pad2-4)") (class "Default")
      (node (ref "N7") (pin "2-4") (pinfunction "4-DC+_2-4") (pintype "bidirectional"))
    )
    (net (code "162") (name "unconnected-(N7B-5-DC++-Pad2-5)") (class "Default")
      (node (ref "N7") (pin "2-5") (pinfunction "5-DC++_2-5") (pintype "bidirectional"))
    )
    (net (code "163") (name "unconnected-(N8B-4-DC+-Pad2-4)") (class "Default")
      (node (ref "N8") (pin "2-4") (pinfunction "4-DC+_2-4") (pintype "bidirectional"))
    )
    (net (code "164") (name "unconnected-(N8B-5-DC++-Pad2-5)") (class "Default")
      (node (ref "N8") (pin "2-5") (pinfunction "5-DC++_2-5") (pintype "bidirectional"))
    )
    (net (code "165") (name "unconnected-(RAICHU-5V-CRIT-INHIBIT-Pad3)") (class "Default")
      (node (ref "RAICHU-5V-CRIT") (pin "3") (pinfunction "INHIBIT_3") (pintype "bidirectional"))
    )
    (net (code "166") (name "unconnected-(U$57-AREF-Pad21)") (class "Default")
      (node (ref "U$57") (pin "21") (pinfunction "AREF_21") (pintype "bidirectional"))
    )
    (net (code "167") (name "unconnected-(U$64-4-DC+-Pad4)") (class "Default")
      (node (ref "U$64") (pin "4") (pinfunction "4-DC+_4") (pintype "bidirectional"))
    )
    (net (code "168") (name "unconnected-(U$64-5-DC++-Pad5)") (class "Default")
      (node (ref "U$64") (pin "5") (pinfunction "5-DC++_5") (pintype "bidirectional"))
    )
  )
)
